# RefOsc10MHz_3V0.net
KiCad netlist of a schematic drawn in EAGLE
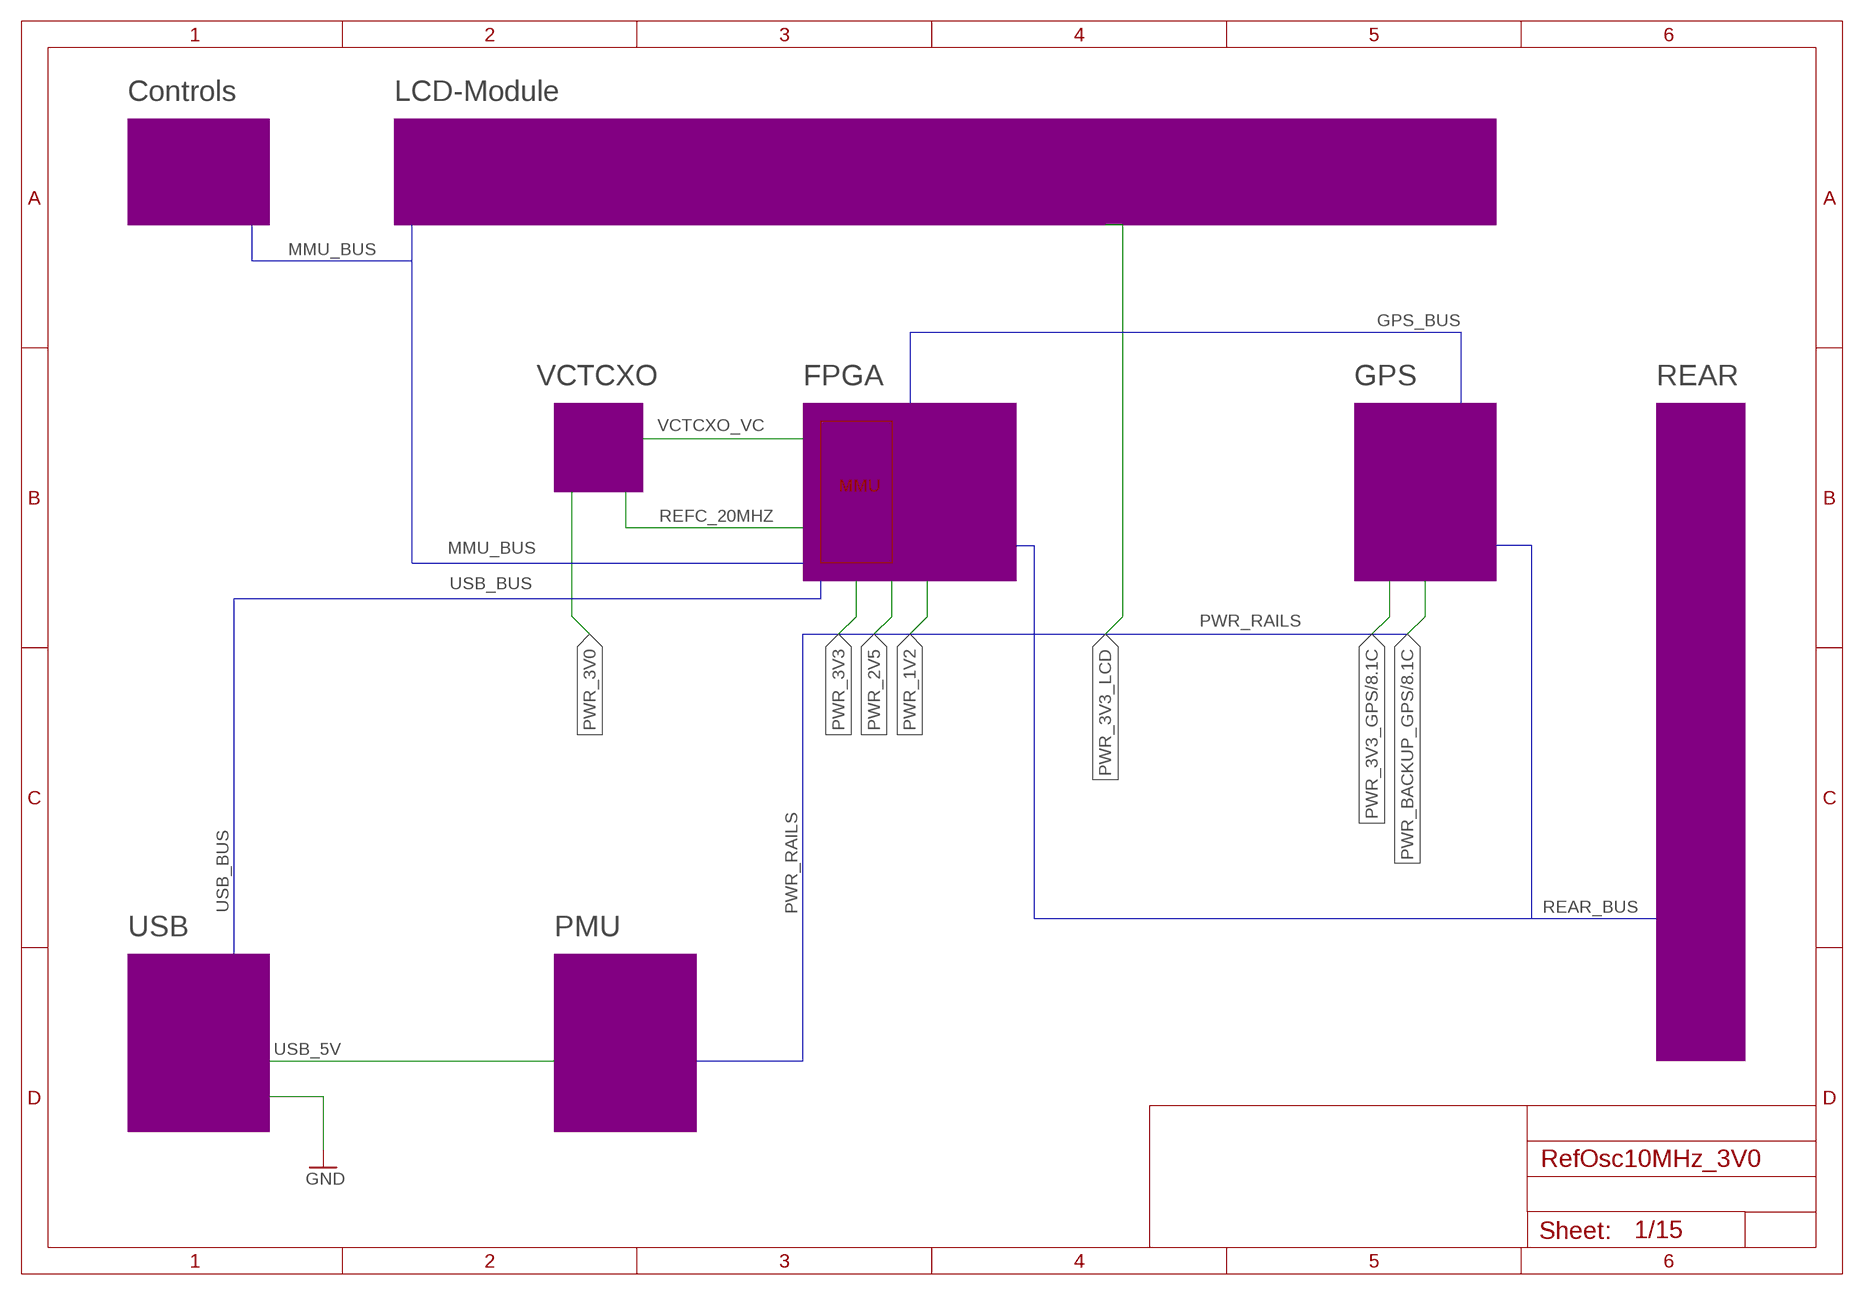
[diagram p0: schematic, sheet 1]
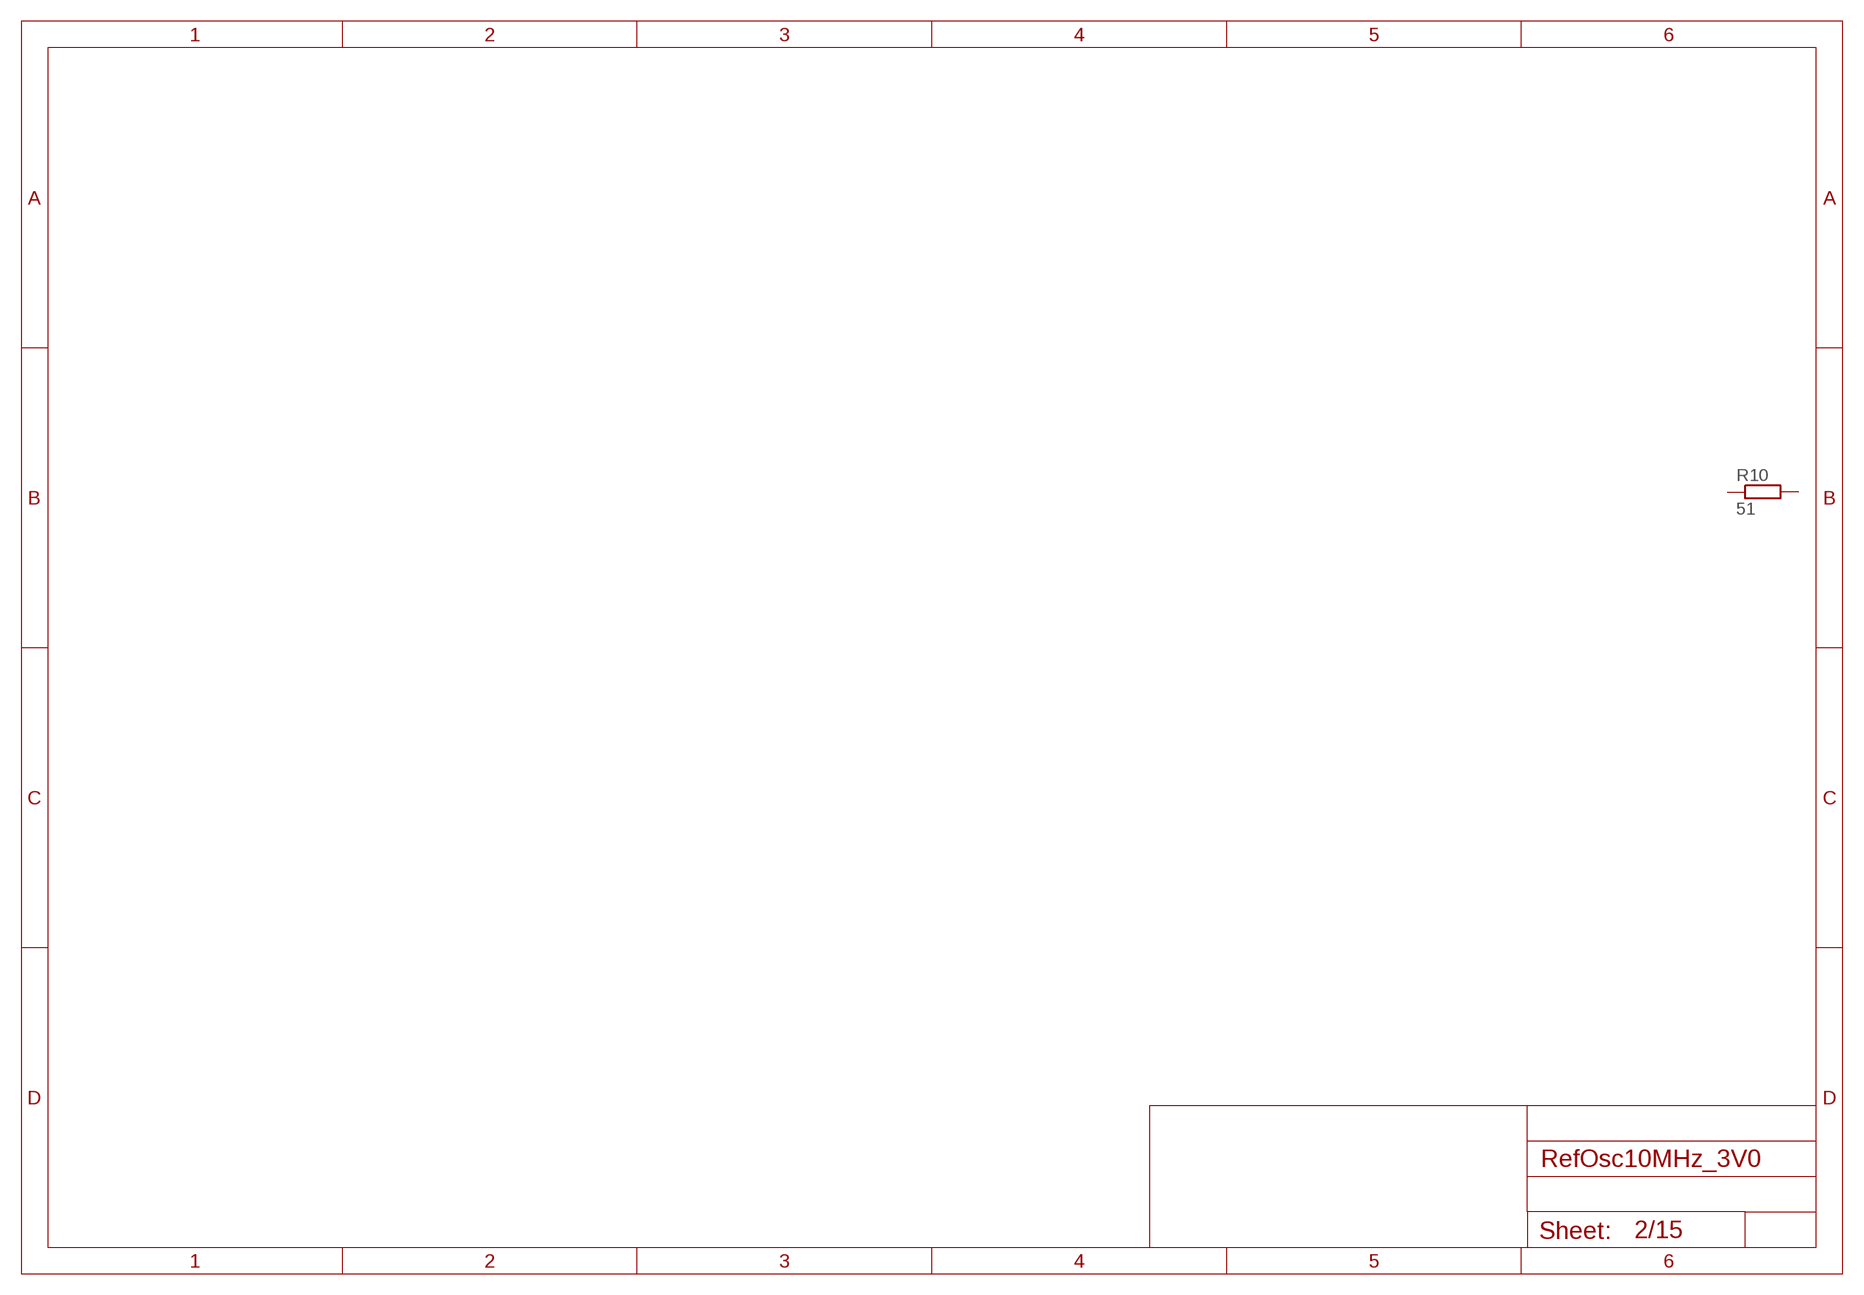
[diagram p1: schematic, sheet 2]
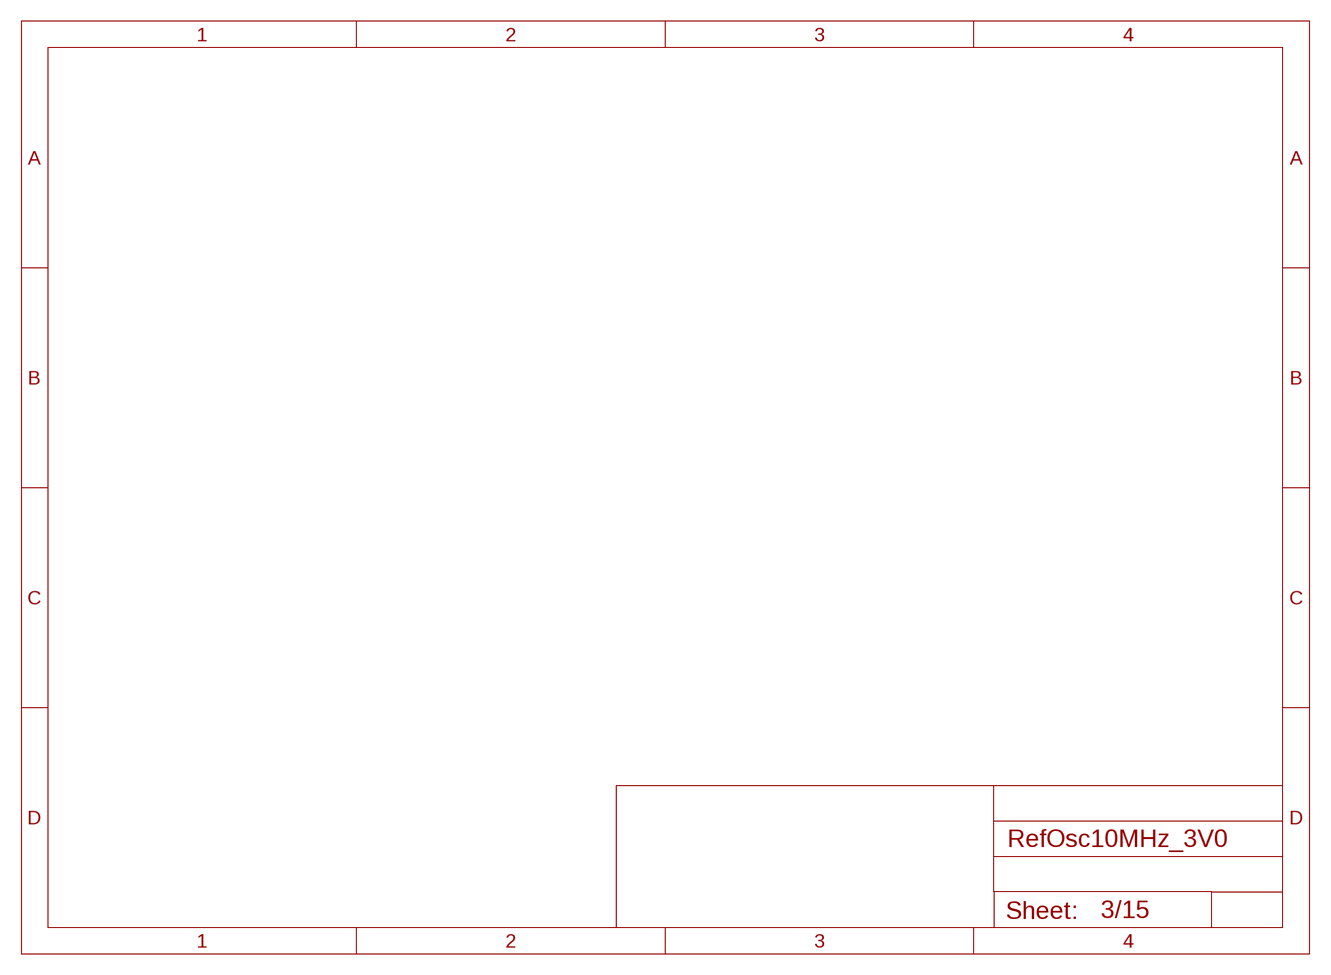
[diagram p2: schematic, sheet 3]
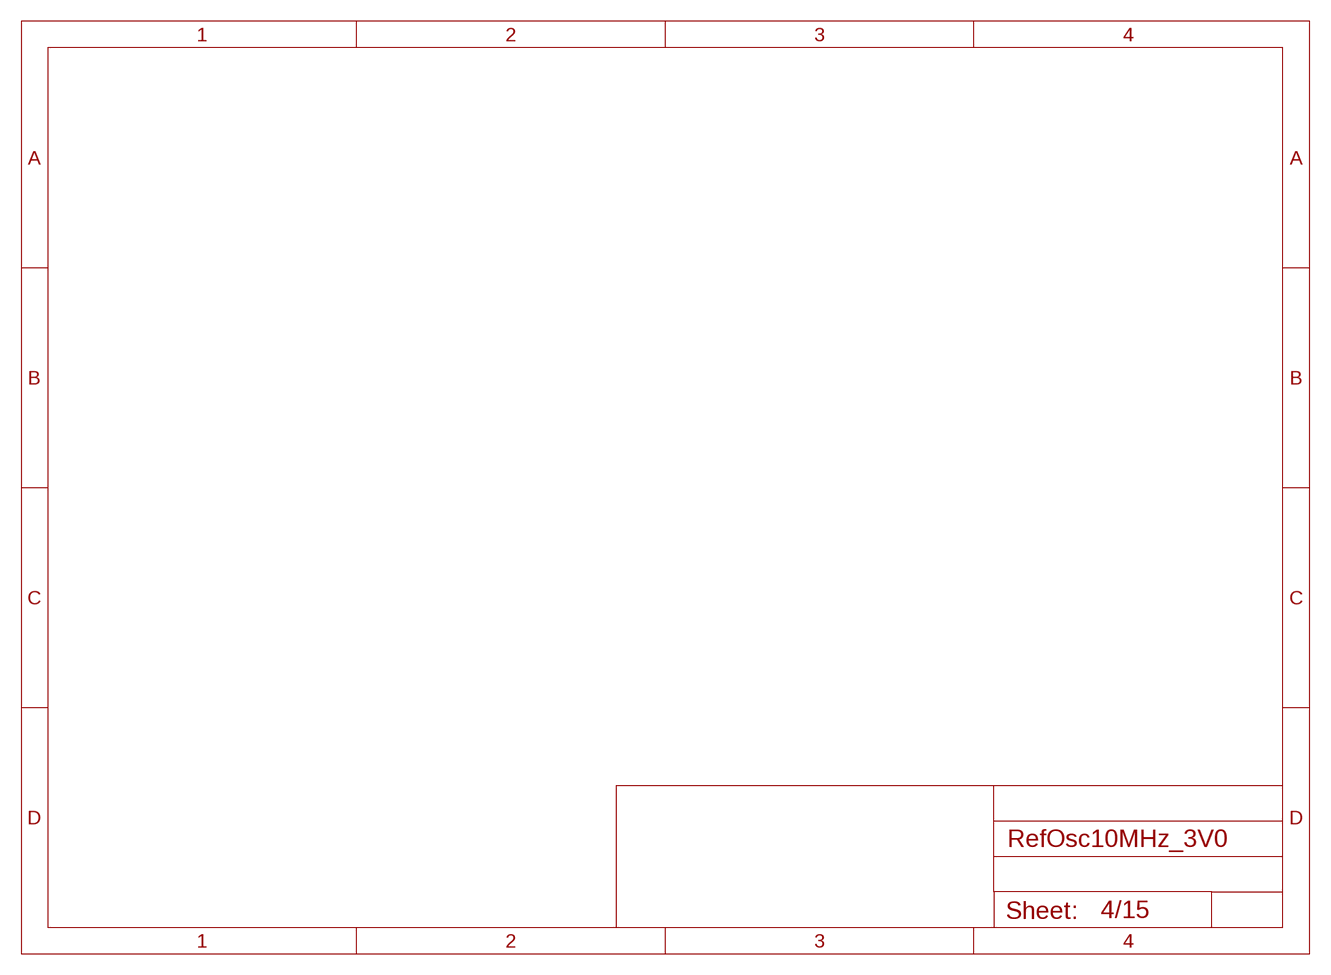
[diagram p3: schematic, sheet 4]
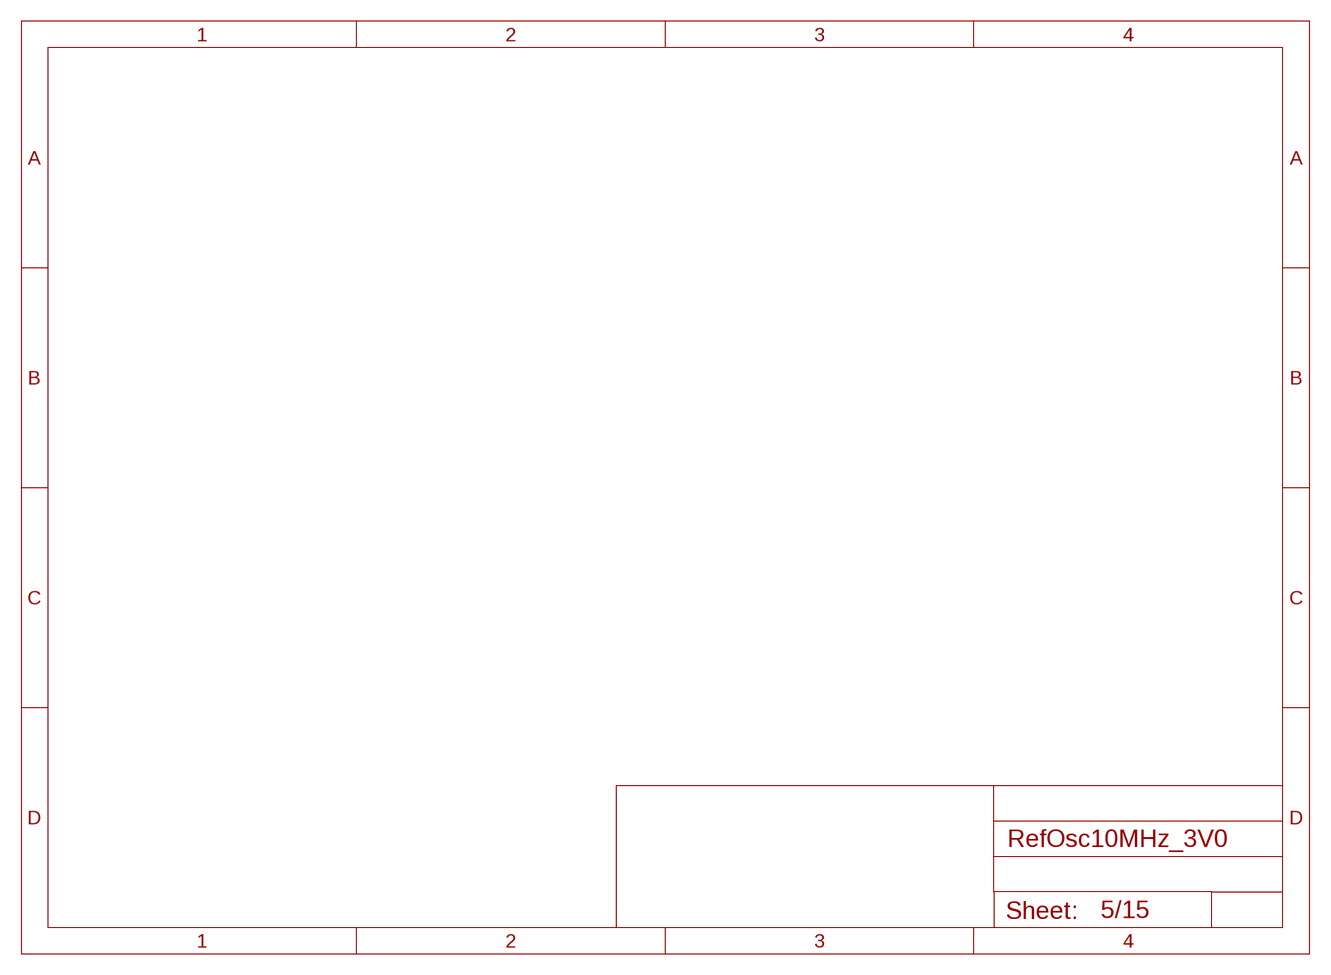
[diagram p4: schematic, sheet 5]
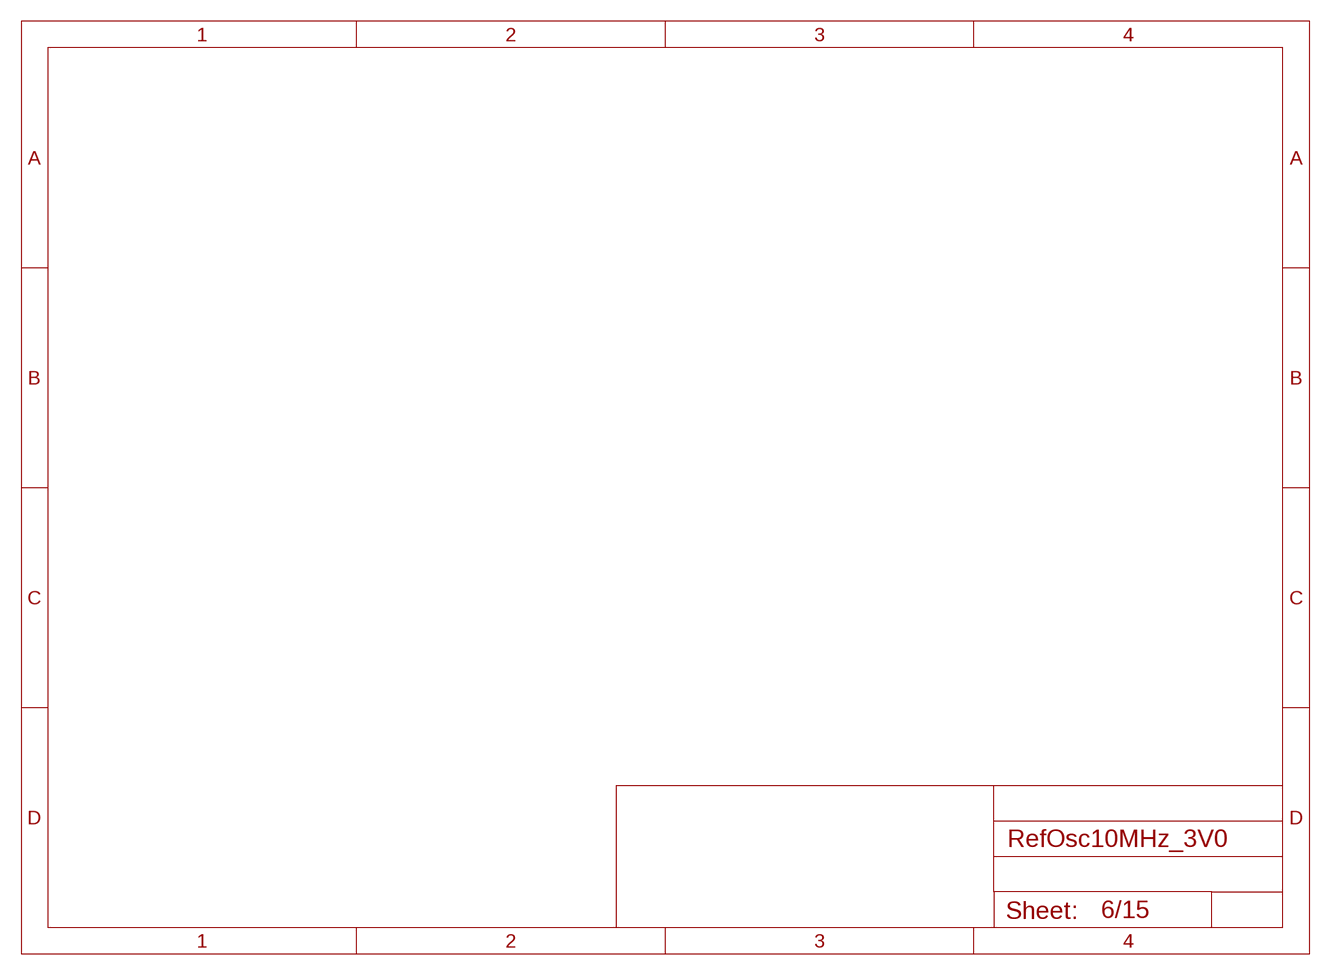
[diagram p5: schematic, sheet 6]
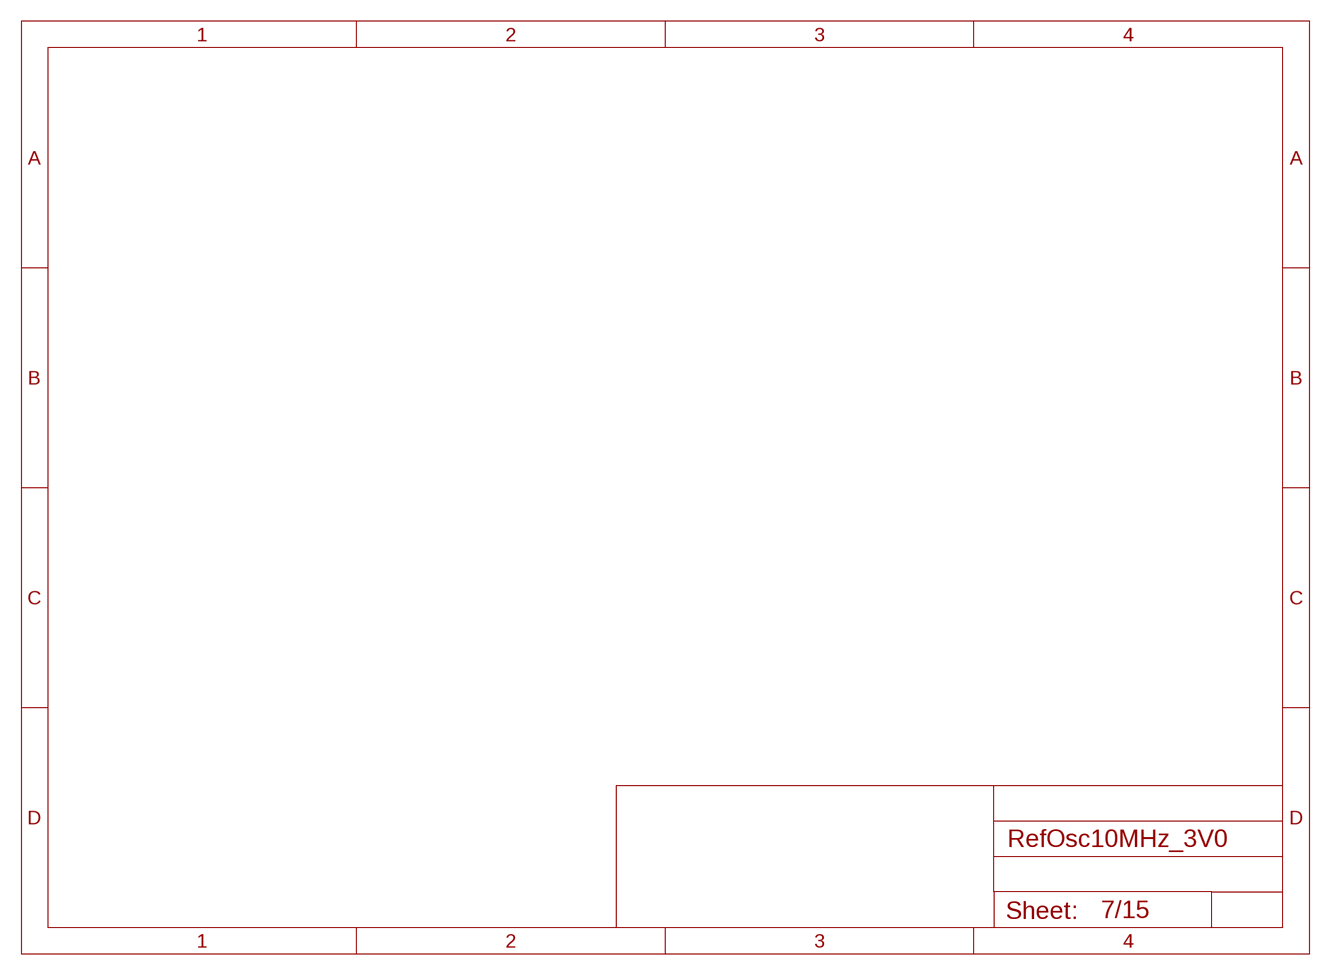
[diagram p6: schematic, sheet 7]
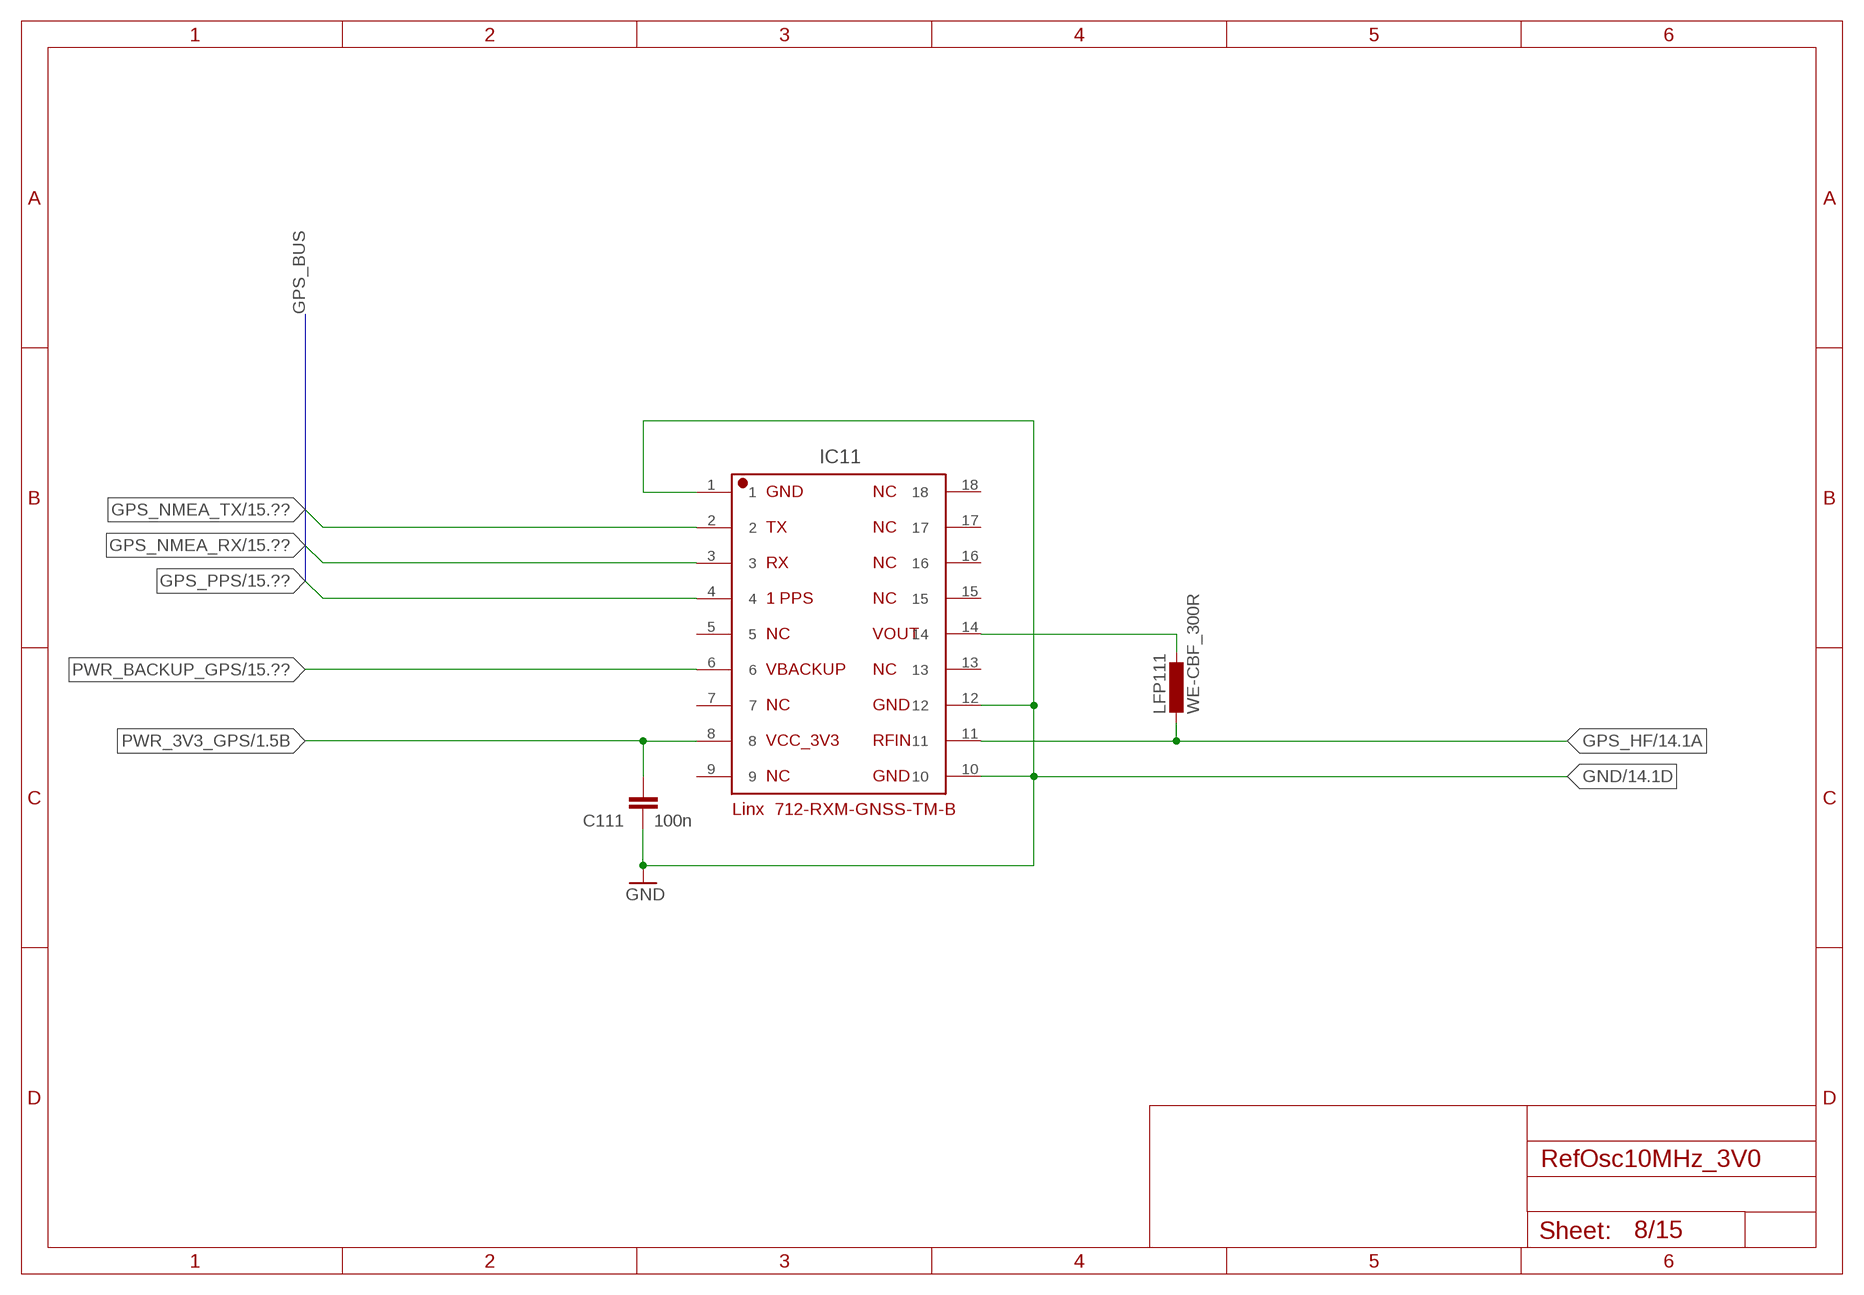
[diagram p7: schematic, sheet 8]
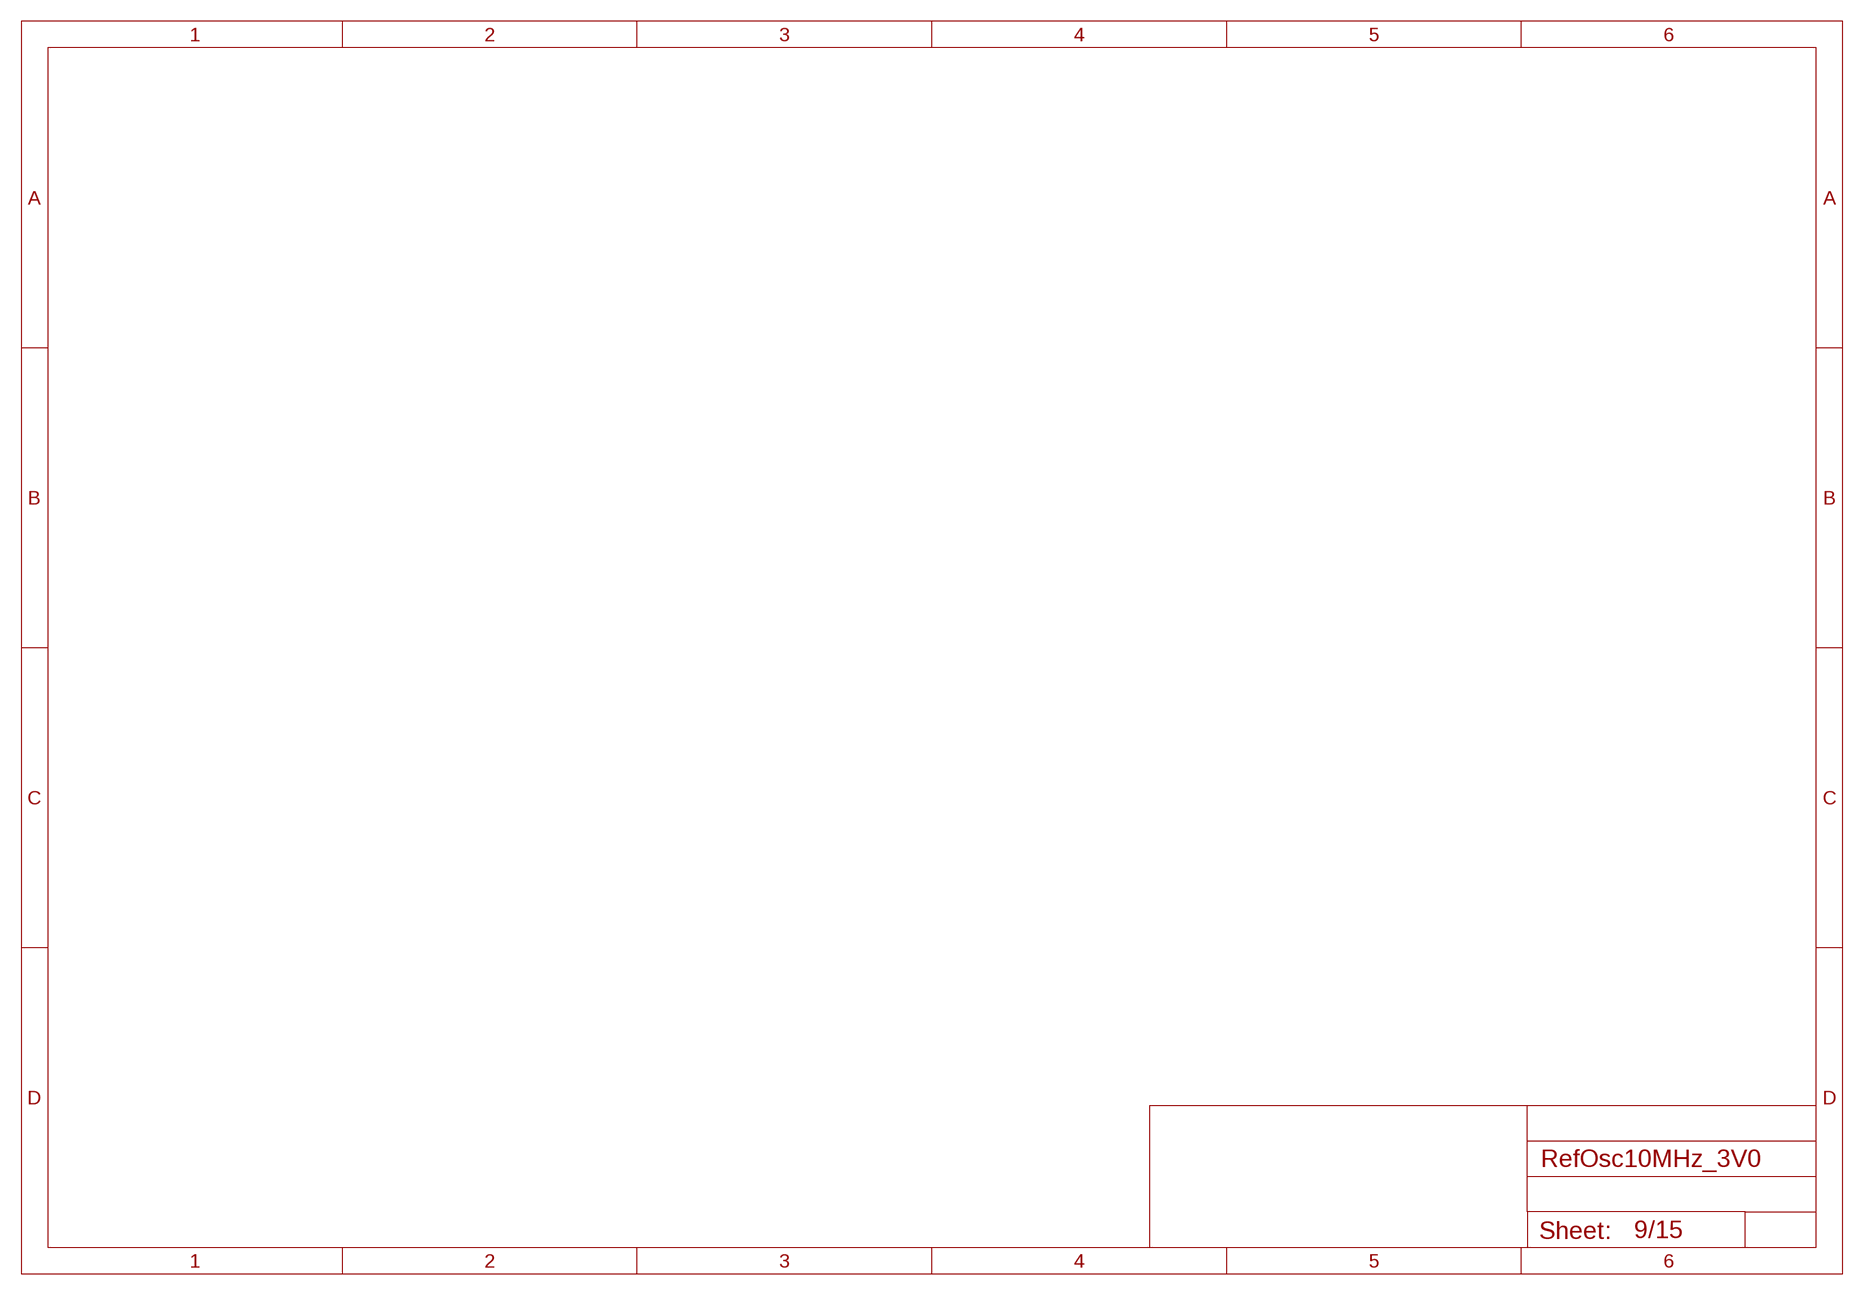
[diagram p8: schematic, sheet 9]
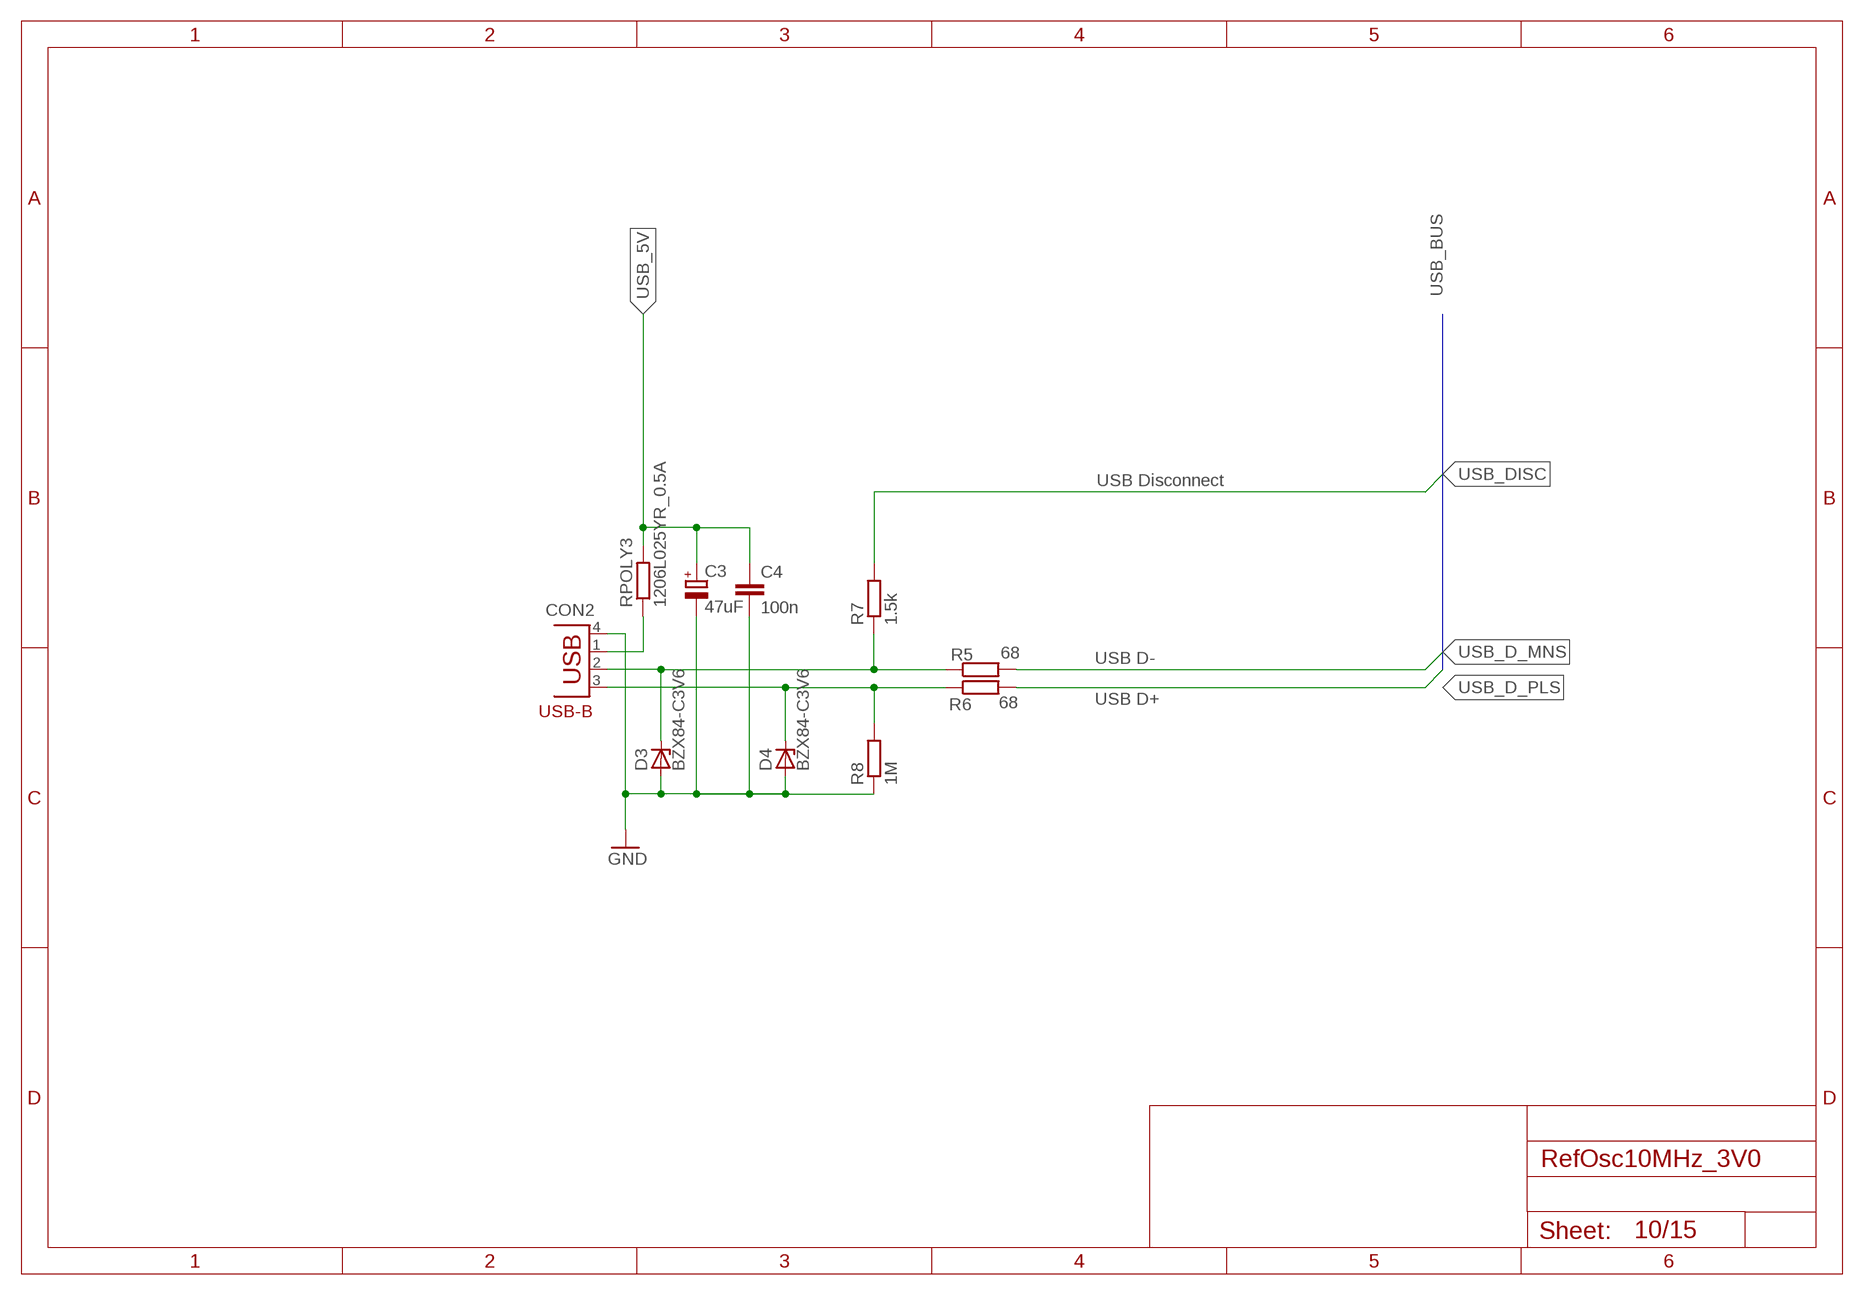
[diagram p9: schematic, sheet 10]
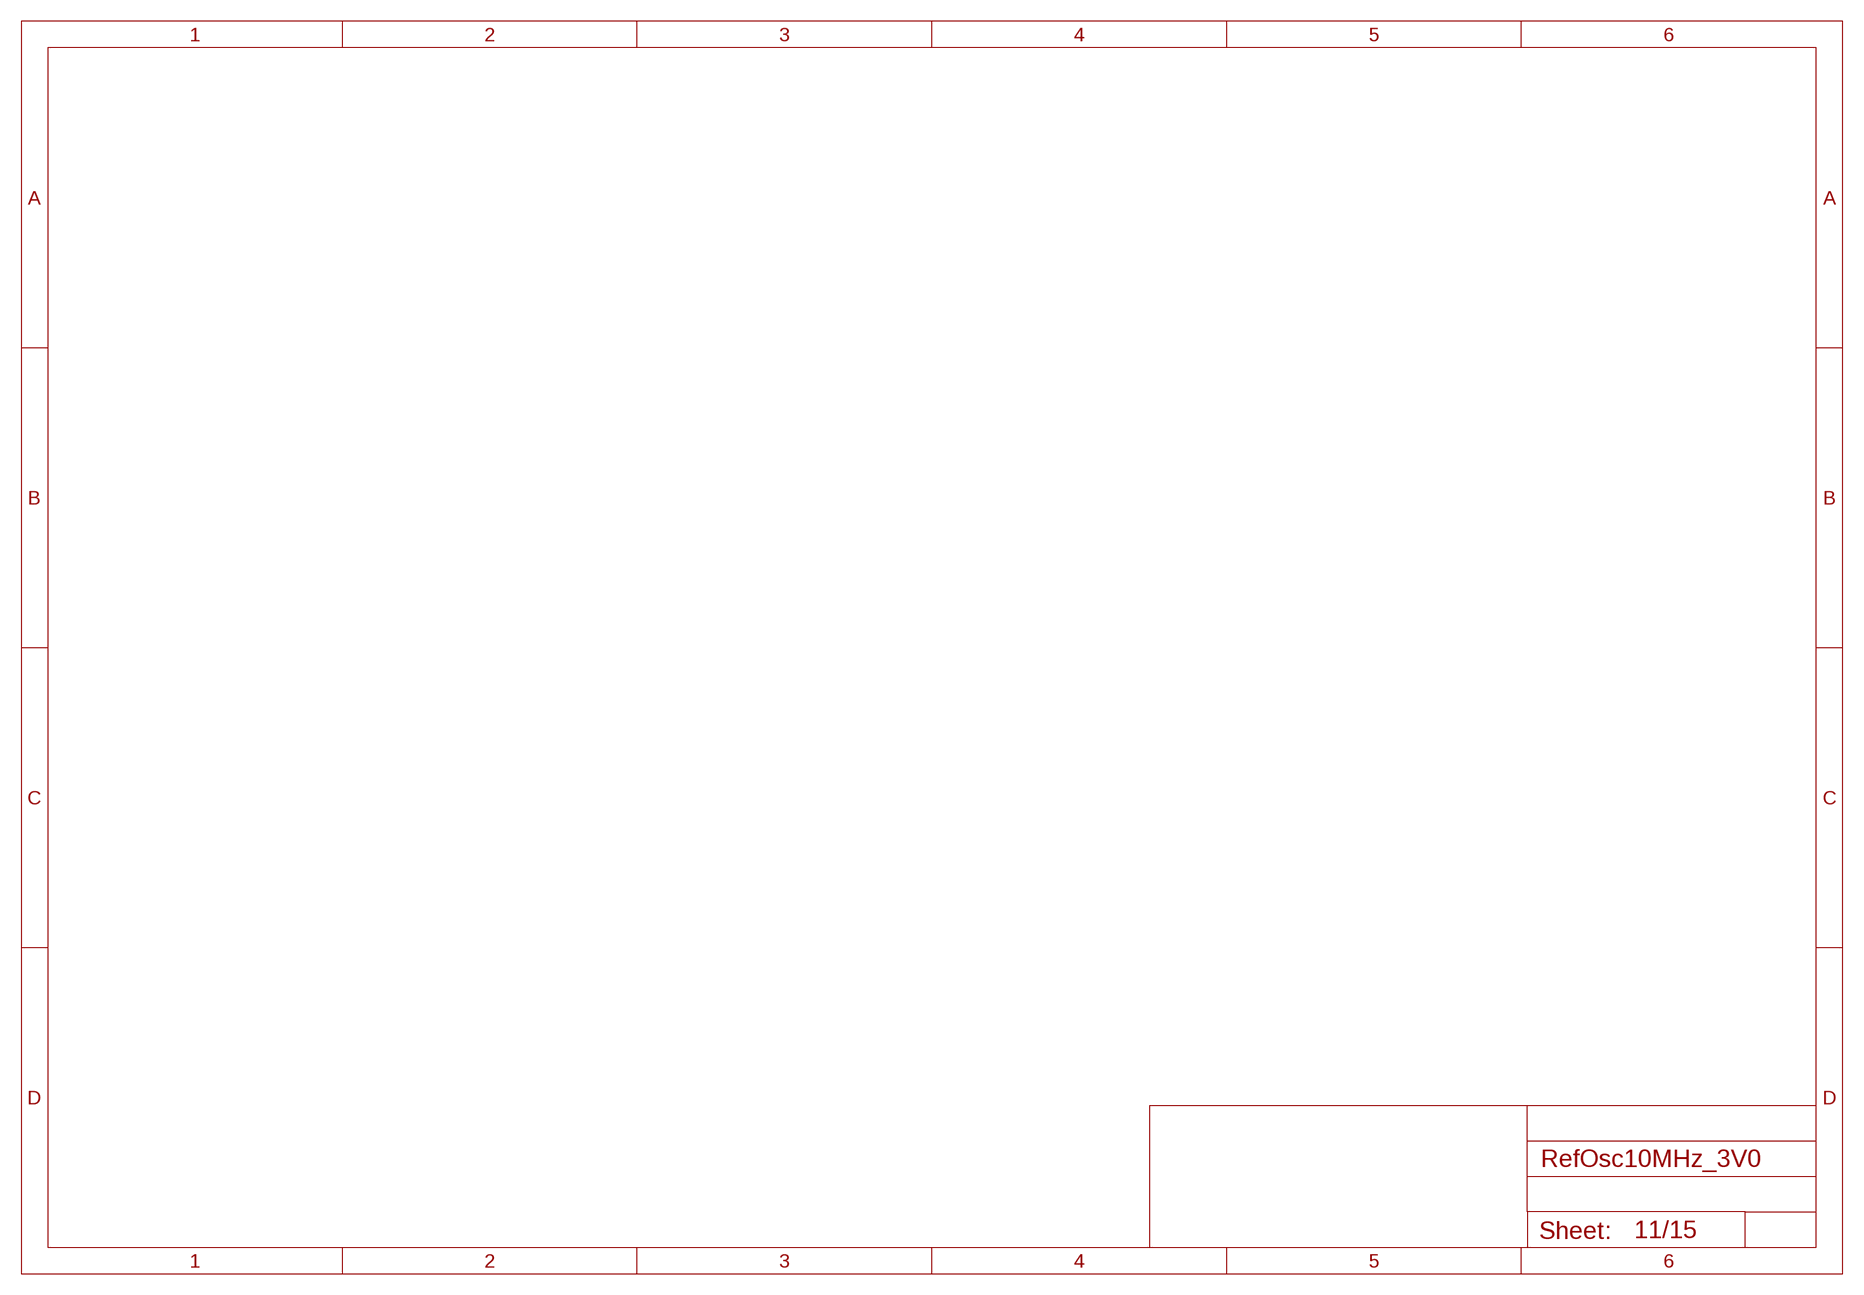
[diagram p10: schematic, sheet 11]
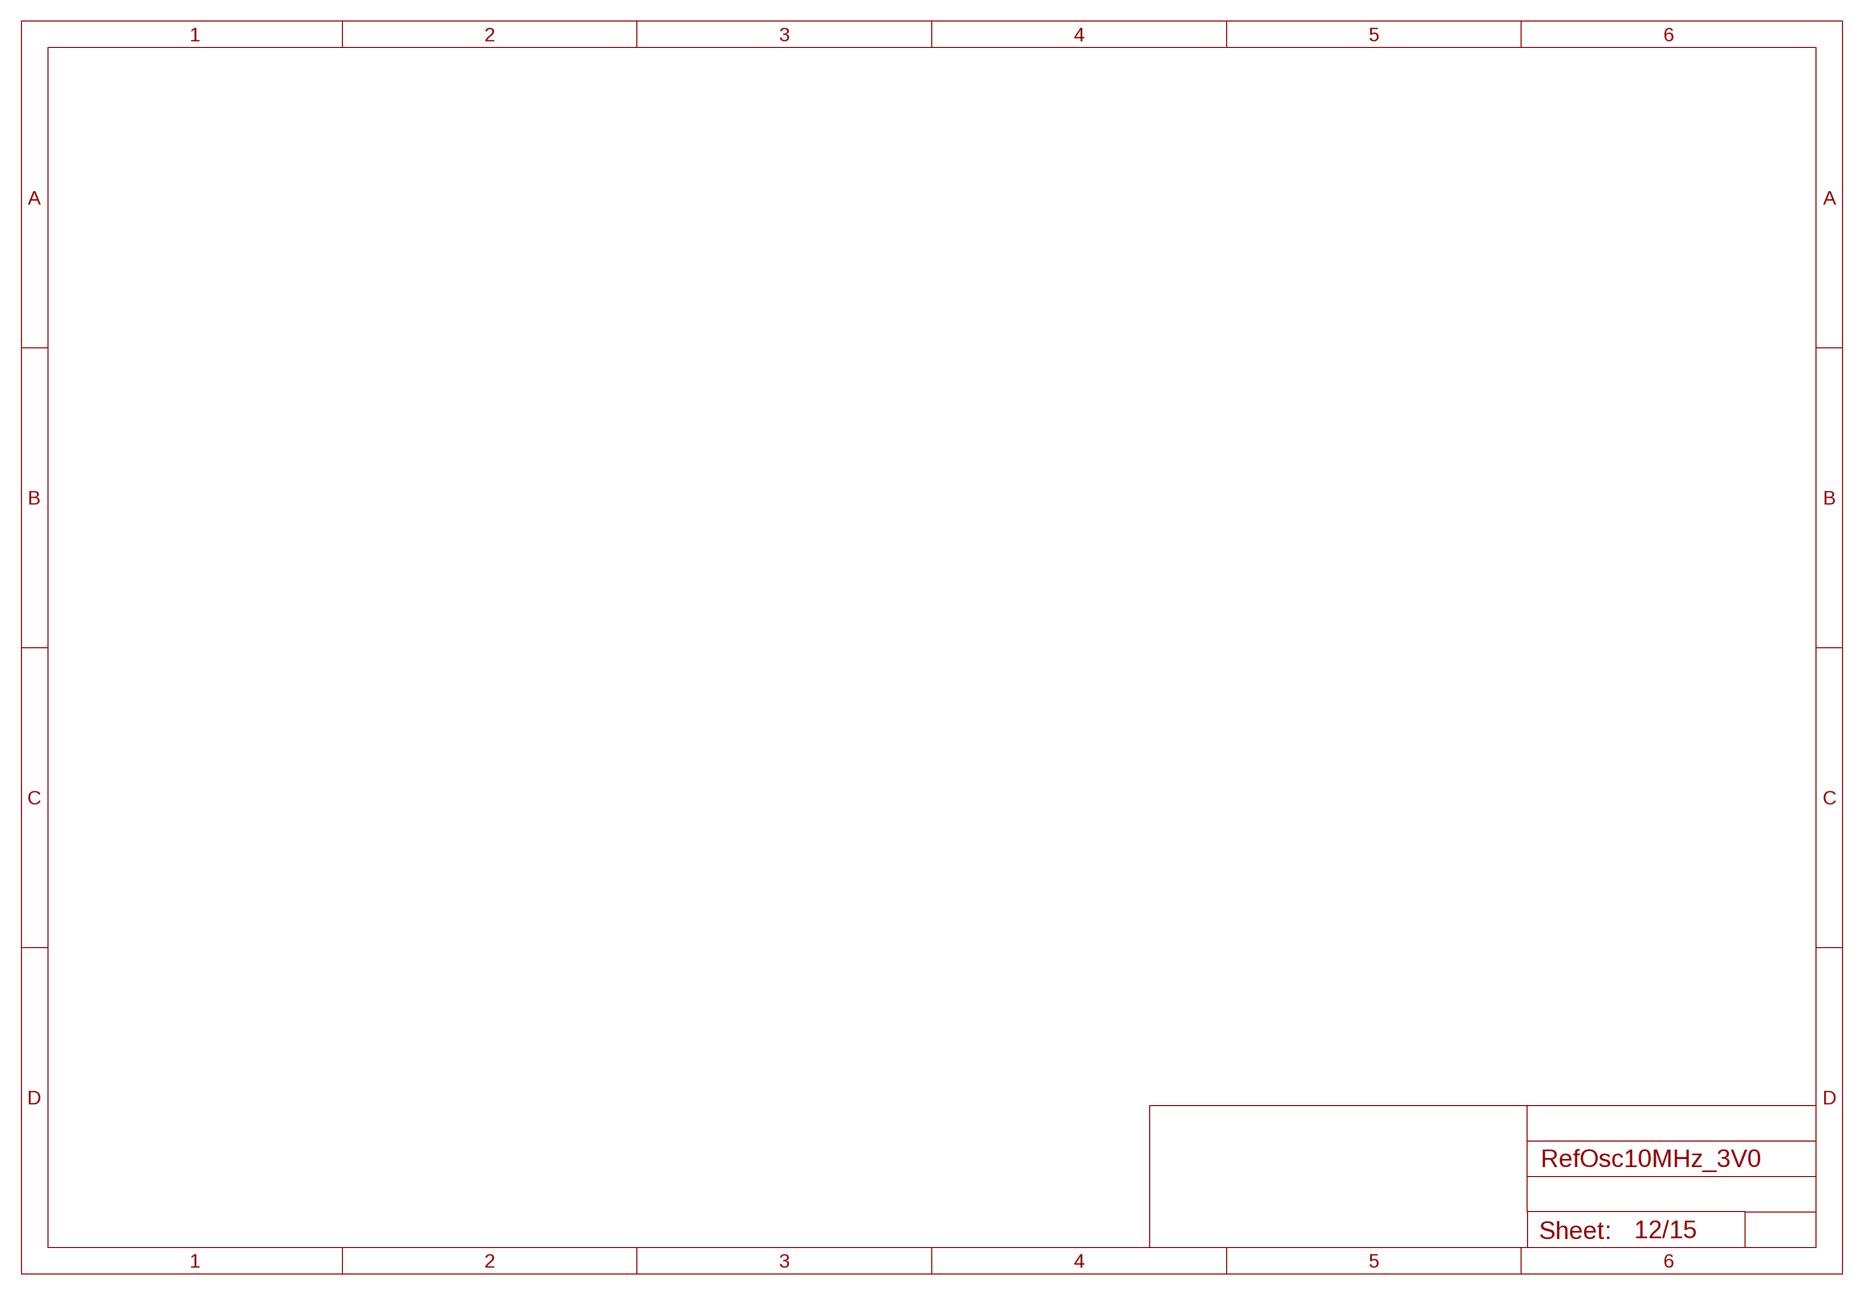
[diagram p11: schematic, sheet 12]
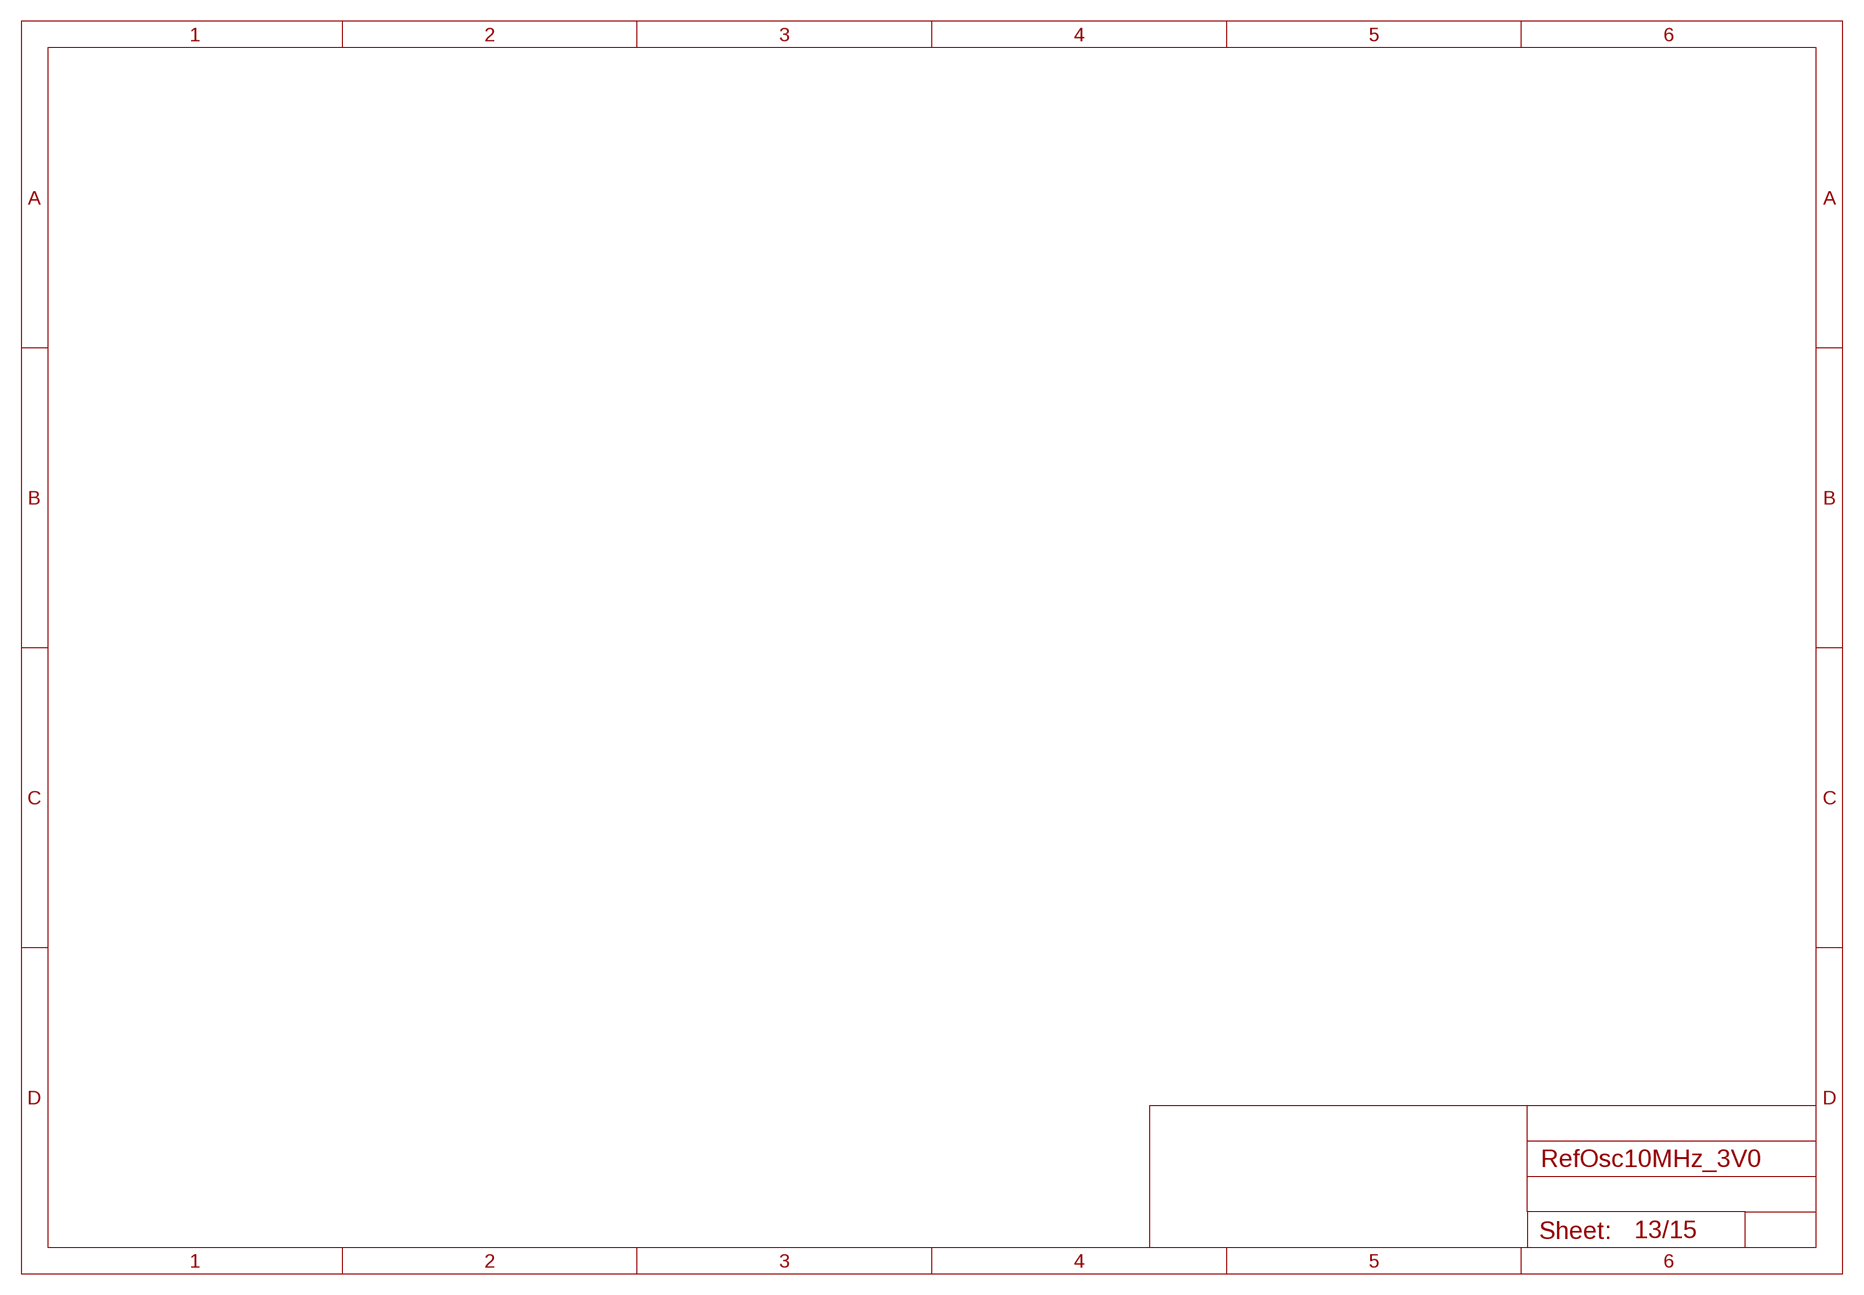
[diagram p12: schematic, sheet 13]
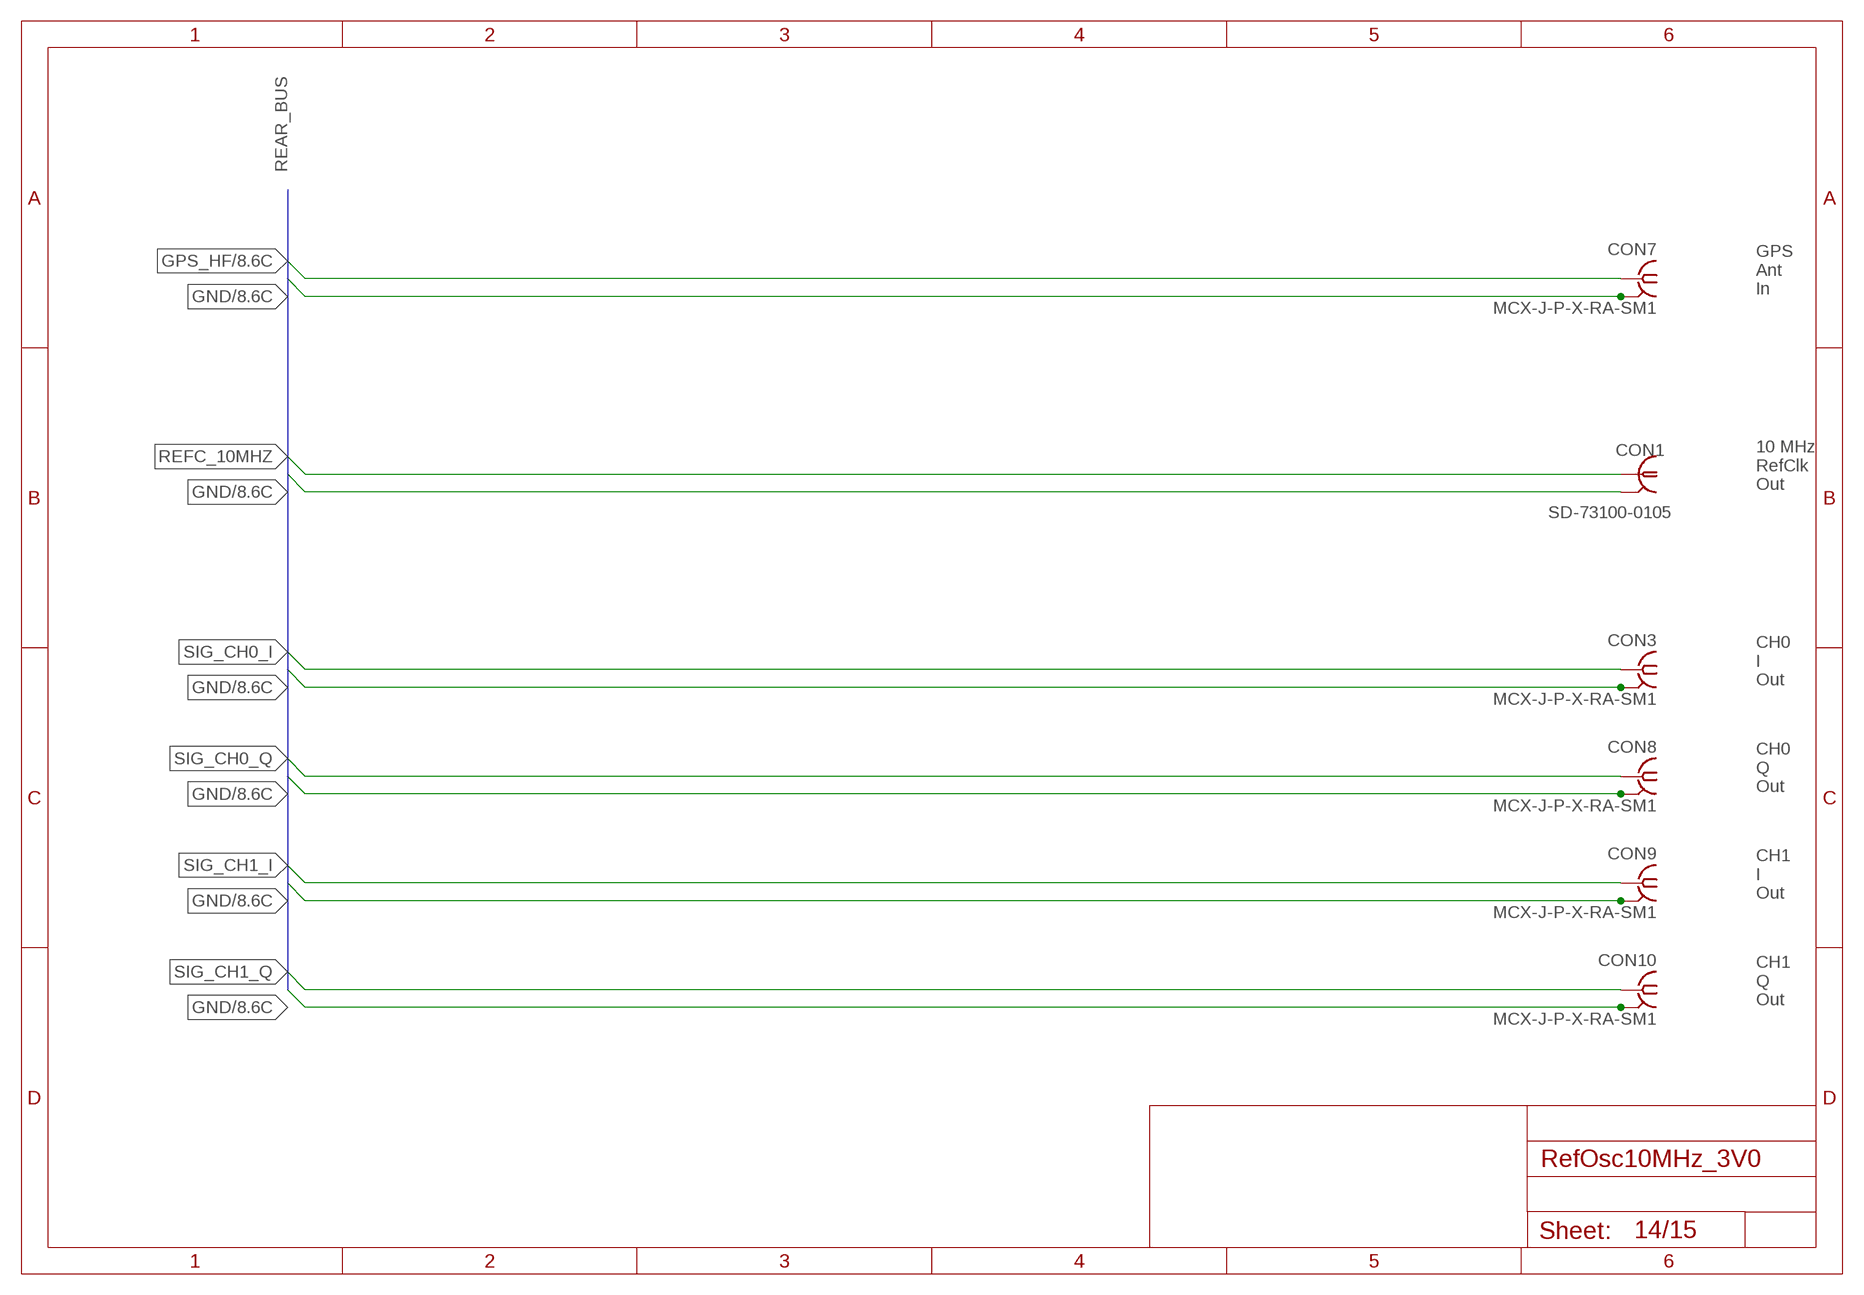
[diagram p13: schematic, sheet 14]
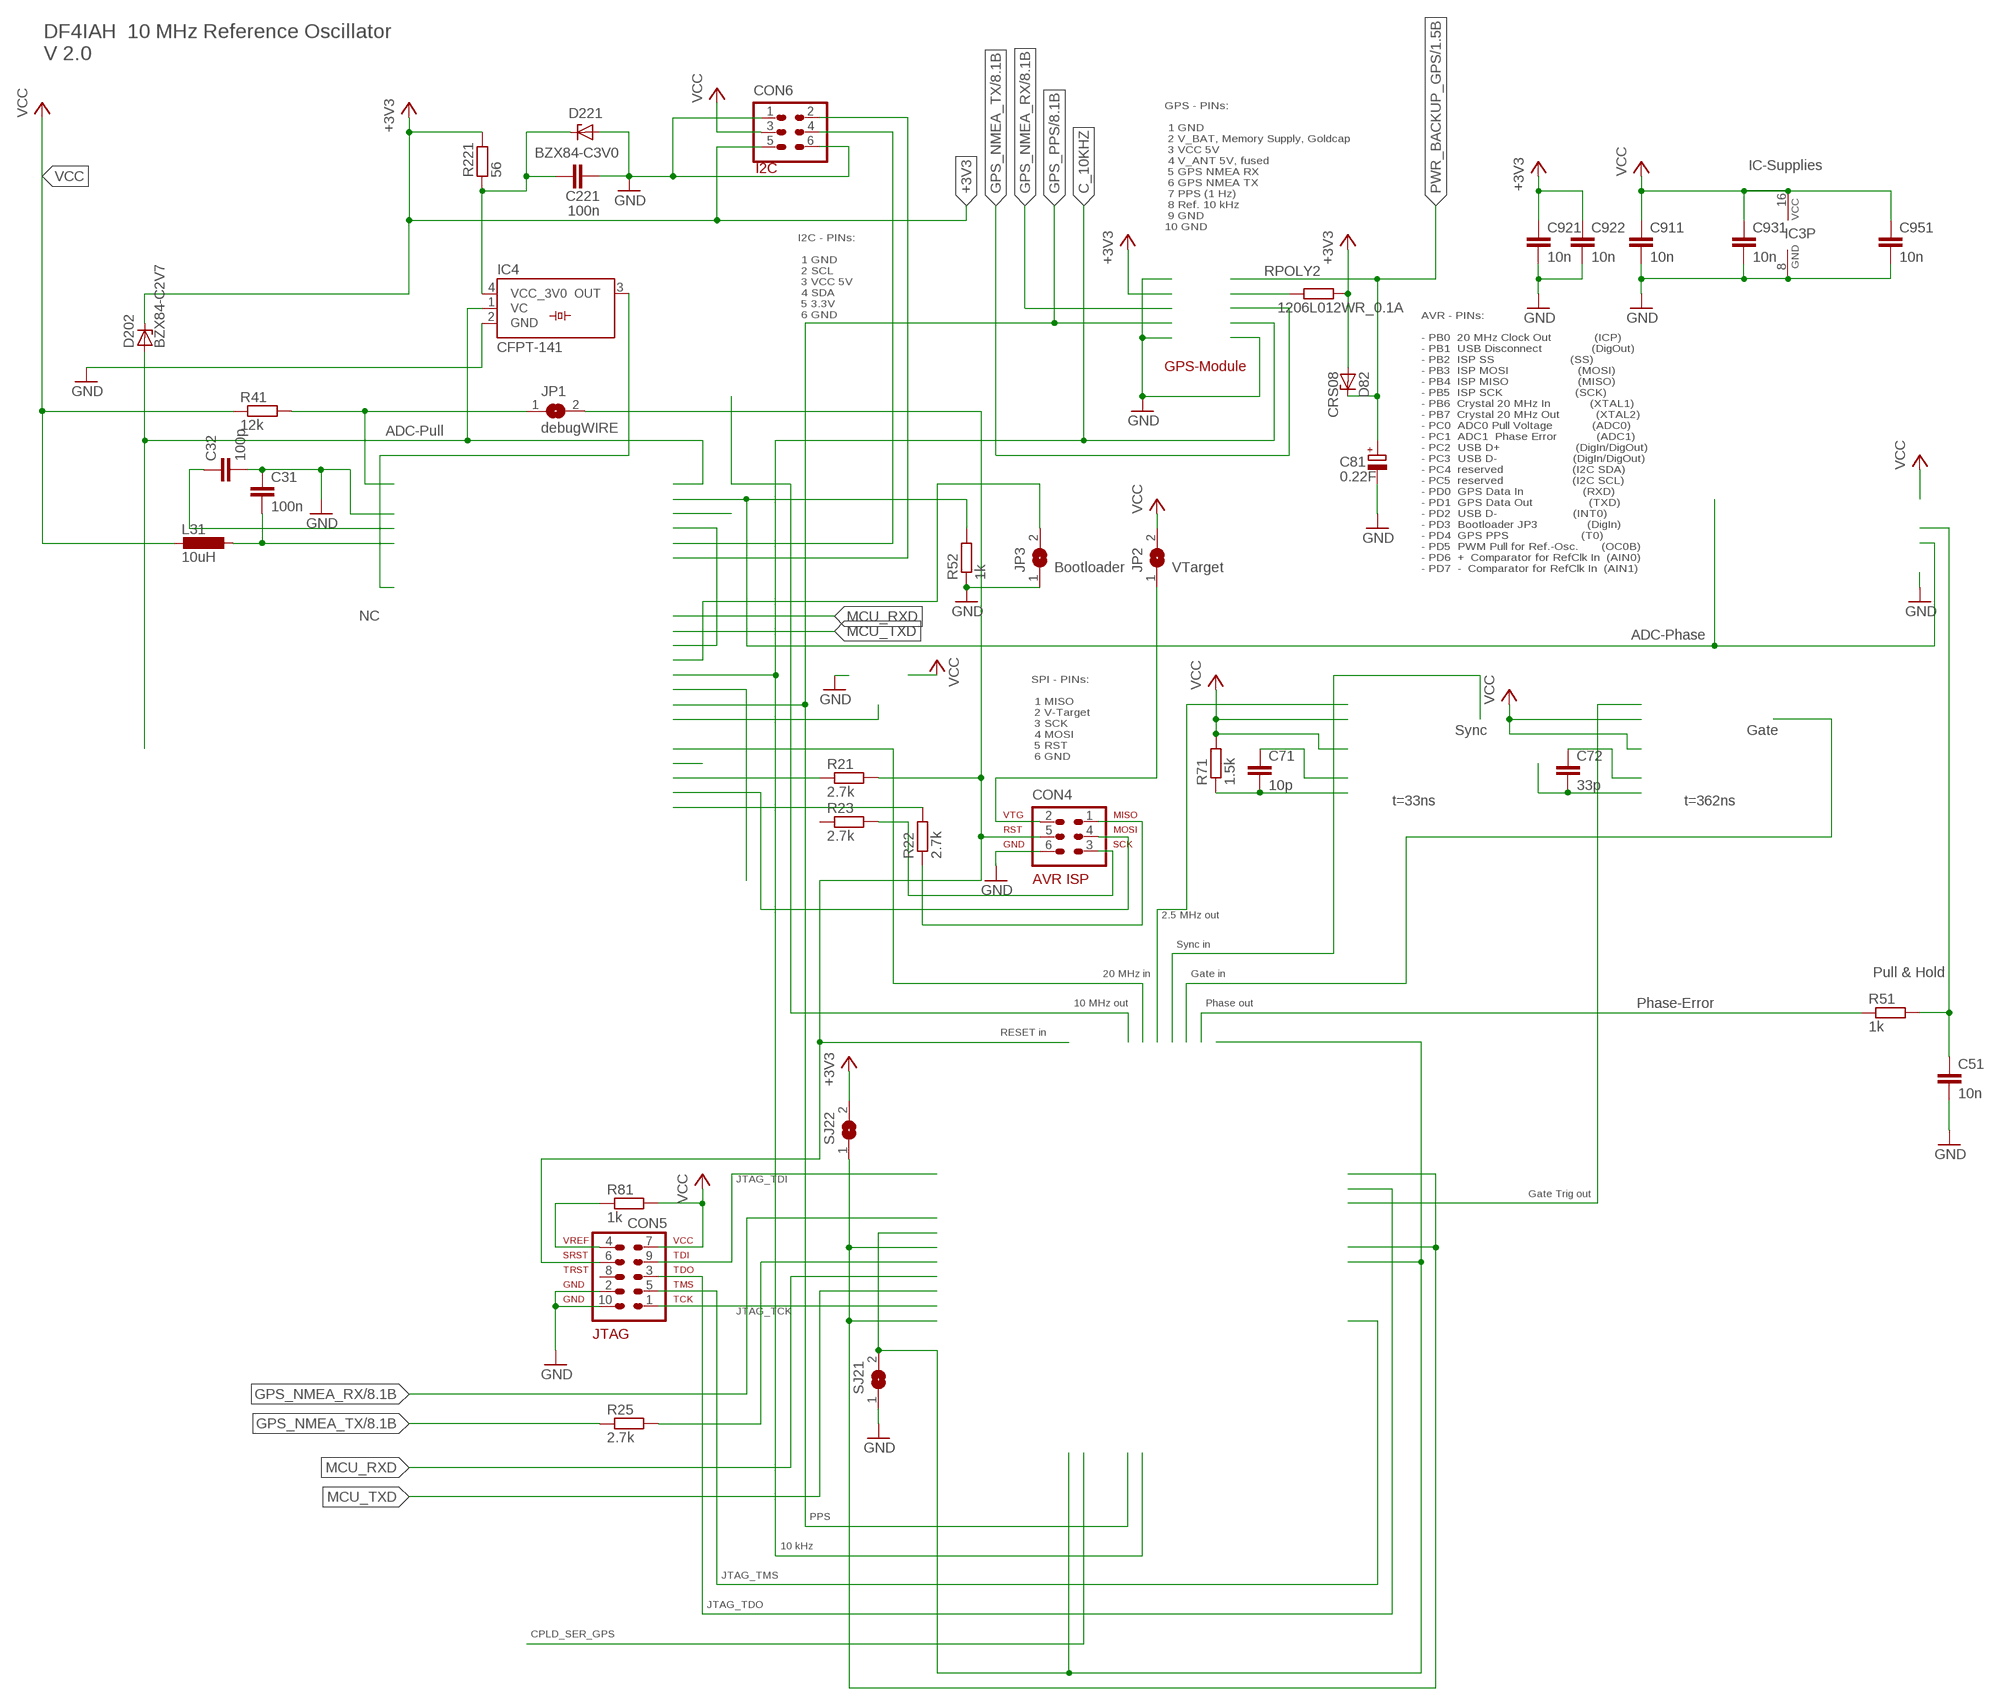
[diagram p14: schematic, sheet 15]

(export (version "E")
  (design (tool "Eeschema 10.0.6"))
  (components
    (comp (ref "CON1")
      (value "SD-73100-0105")
      (footprint "eagle-import:MOLEX_BNC-JACK-50R_SD-73100-0105")
      (fields (field (name "MF") "MOLEX"))
      (libsource (lib "eagle-import") (part "MOLEX_BNC-JACK-50R_SD-73100-0105"))
    )
    (comp (ref "CON3")
      (value "MCX-J-P-X-RA-SM1")
      (footprint "eagle-import:MCX-J-P-X-RA-SM1")
      (libsource (lib "eagle-import") (part "MCX-J-P-X-RA-SM1"))
    )
    (comp (ref "CON7")
      (value "MCX-J-P-X-RA-SM1")
      (footprint "eagle-import:MCX-J-P-X-RA-SM1")
      (libsource (lib "eagle-import") (part "MCX-J-P-X-RA-SM1"))
    )
    (comp (ref "CON8")
      (value "MCX-J-P-X-RA-SM1")
      (footprint "eagle-import:MCX-J-P-X-RA-SM1")
      (libsource (lib "eagle-import") (part "MCX-J-P-X-RA-SM1"))
    )
    (comp (ref "CON9")
      (value "MCX-J-P-X-RA-SM1")
      (footprint "eagle-import:MCX-J-P-X-RA-SM1")
      (libsource (lib "eagle-import") (part "MCX-J-P-X-RA-SM1"))
    )
    (comp (ref "CON10")
      (value "MCX-J-P-X-RA-SM1")
      (footprint "eagle-import:MCX-J-P-X-RA-SM1")
      (libsource (lib "eagle-import") (part "MCX-J-P-X-RA-SM1"))
    )
    (comp (ref "C31")
      (value "100n")
      (footprint "eagle-import:C0805")
      (libsource (lib "eagle-import") (part "rcl_C-EUC0805"))
    )
    (comp (ref "C32")
      (value "100p")
      (footprint "eagle-import:C0805")
      (libsource (lib "eagle-import") (part "rcl_C-EUC0805"))
    )
    (comp (ref "C51")
      (value "10n")
      (footprint "eagle-import:C0805")
      (libsource (lib "eagle-import") (part "rcl_C-EUC0805"))
    )
    (comp (ref "C71")
      (value "10p")
      (footprint "eagle-import:C0805")
      (libsource (lib "eagle-import") (part "rcl_C-EUC0805"))
    )
    (comp (ref "C72")
      (value "33p")
      (footprint "eagle-import:C0805")
      (libsource (lib "eagle-import") (part "rcl_C-EUC0805"))
    )
    (comp (ref "C81")
      (value "0.22F")
      (footprint "eagle-import:PANASONIC_C")
      (libsource (lib "eagle-import") (part "CPOL-EUC"))
    )
    (comp (ref "C221")
      (value "100n")
      (footprint "eagle-import:C0805")
      (libsource (lib "eagle-import") (part "rcl_C-EUC0805"))
    )
    (comp (ref "C911")
      (value "10n")
      (footprint "eagle-import:C0805")
      (libsource (lib "eagle-import") (part "rcl_C-EUC0805"))
    )
    (comp (ref "C921")
      (value "10n")
      (footprint "eagle-import:C0805")
      (libsource (lib "eagle-import") (part "rcl_C-EUC0805"))
    )
    (comp (ref "C922")
      (value "10n")
      (footprint "eagle-import:C0805")
      (libsource (lib "eagle-import") (part "rcl_C-EUC0805"))
    )
    (comp (ref "C931")
      (value "10n")
      (footprint "eagle-import:C0805")
      (libsource (lib "eagle-import") (part "rcl_C-EUC0805"))
    )
    (comp (ref "C951")
      (value "10n")
      (footprint "eagle-import:C0805")
      (libsource (lib "eagle-import") (part "rcl_C-EUC0805"))
    )
    (comp (ref "CON4")
      (value "AVR-ISP-6SMD")
      (footprint "eagle-import:2X3SMD")
      (libsource (lib "eagle-import") (part "AVR-ISP-6SMD"))
    )
    (comp (ref "CON5")
      (value "AVR-JTAG-10SMD")
      (footprint "eagle-import:2X5SMD")
      (libsource (lib "eagle-import") (part "AVR-JTAG-10SMD"))
    )
    (comp (ref "CON6")
      (value "HEADER-2X3SMD")
      (footprint "eagle-import:2X03SMD")
      (libsource (lib "eagle-import") (part "HEADER-2X3SMD"))
    )
    (comp (ref "D82")
      (value "CRS08")
      (footprint "eagle-import:SOT23")
      (libsource (lib "eagle-import") (part "ZENER-DIODESOT23"))
    )
    (comp (ref "D202")
      (value "BZX84-C2V7")
      (footprint "eagle-import:TO236")
      (libsource (lib "eagle-import") (part "BZX84CSMD"))
    )
    (comp (ref "D221")
      (value "BZX84-C3V0")
      (footprint "eagle-import:TO236")
      (libsource (lib "eagle-import") (part "BZX84CSMD"))
    )
    (comp (ref "IC3")
      (value "74HCT221D")
      (footprint "eagle-import:SO16")
      (libsource (lib "eagle-import") (part "74221DHCT"))
    )
    (comp (ref "IC4")
      (value "CFPT-141")
      (footprint "eagle-import:CFPT-141")
      (fields (field (name "MF") "IQD-FREQUENCY-PRODUCTS") (field (name "MPN") "LFTVXO022175"))
      (libsource (lib "eagle-import") (part "CFPT-141"))
    )
    (comp (ref "JP1")
      (value "SJW")
      (footprint "eagle-import:SJW")
      (libsource (lib "eagle-import") (part "SJW"))
    )
    (comp (ref "JP2")
      (value "SJW")
      (footprint "eagle-import:SJW")
      (libsource (lib "eagle-import") (part "SJW"))
    )
    (comp (ref "JP3")
      (value "SJW")
      (footprint "eagle-import:SJW")
      (libsource (lib "eagle-import") (part "SJW"))
    )
    (comp (ref "L31")
      (value "10uH")
      (footprint "eagle-import:L1812")
      (libsource (lib "eagle-import") (part "rcl_L-EUL1812"))
    )
    (comp (ref "R21")
      (value "2.7k")
      (footprint "eagle-import:R0805")
      (libsource (lib "eagle-import") (part "R-EU_R0805"))
    )
    (comp (ref "R22")
      (value "2.7k")
      (footprint "eagle-import:R0805")
      (libsource (lib "eagle-import") (part "R-EU_R0805"))
    )
    (comp (ref "R23")
      (value "2.7k")
      (footprint "eagle-import:R0805")
      (libsource (lib "eagle-import") (part "R-EU_R0805"))
    )
    (comp (ref "R25")
      (value "2.7k")
      (footprint "eagle-import:R0805")
      (libsource (lib "eagle-import") (part "R-EU_R0805"))
    )
    (comp (ref "R41")
      (value "12k")
      (footprint "eagle-import:R0805")
      (libsource (lib "eagle-import") (part "R-EU_R0805"))
    )
    (comp (ref "R51")
      (value "1k")
      (footprint "eagle-import:R0805")
      (libsource (lib "eagle-import") (part "R-EU_R0805"))
    )
    (comp (ref "R52")
      (value "1k")
      (footprint "eagle-import:R0805")
      (libsource (lib "eagle-import") (part "R-EU_R0805"))
    )
    (comp (ref "R71")
      (value "1.5k")
      (footprint "eagle-import:R0805")
      (libsource (lib "eagle-import") (part "R-EU_R0805"))
    )
    (comp (ref "R81")
      (value "1k")
      (footprint "eagle-import:R0805")
      (libsource (lib "eagle-import") (part "R-EU_R0805"))
    )
    (comp (ref "R221")
      (value "56")
      (footprint "eagle-import:R0805")
      (libsource (lib "eagle-import") (part "R-EU_R0805"))
    )
    (comp (ref "RPOLY2")
      (value "1206L012WR_0.1A")
      (footprint "eagle-import:M1206")
      (libsource (lib "eagle-import") (part "R-EU_M1206"))
    )
    (comp (ref "SJ21")
      (value "SJ")
      (footprint "eagle-import:SJ")
      (libsource (lib "eagle-import") (part "SJ"))
    )
    (comp (ref "SJ22")
      (value "SJ")
      (footprint "eagle-import:SJ")
      (libsource (lib "eagle-import") (part "SJ"))
    )
    (comp (ref "C111")
      (value "100n")
      (footprint "eagle-import:C0805")
      (libsource (lib "eagle-import") (part "C-EUC0805"))
    )
    (comp (ref "IC11")
      (value "712-RXM-GNSS-TM-B")
      (footprint "eagle-import:712-RXM-GNSS-TM-B")
      (libsource (lib "eagle-import") (part "712-RXM-GNSS-TM-B"))
    )
    (comp (ref "LFP111")
      (value "WE-CBF_300R")
      (footprint "eagle-import:L3216C")
      (libsource (lib "eagle-import") (part "L-EUL3216C"))
    )
    (comp (ref "R10")
      (value "51")
      (footprint "eagle-import:R0805")
      (libsource (lib "eagle-import") (part "R-EU_R0805"))
    )
    (comp (ref "C3")
      (value "47uF")
      (footprint "eagle-import:PANASONIC_C")
      (libsource (lib "eagle-import") (part "CPOL-EUC"))
    )
    (comp (ref "C4")
      (value "100n")
      (footprint "eagle-import:C0805")
      (libsource (lib "eagle-import") (part "rcl_C-EUC0805"))
    )
    (comp (ref "CON2")
      (value "TYCO-AMP_USBUSB-B_SMT")
      (footprint "eagle-import:TYCO-AMP_USB-B_SMT")
      (fields (field (name "MF") "TYCO-AMP") (field (name "MPN") "1734346"))
      (libsource (lib "eagle-import") (part "TYCO-AMP_USBUSB-B_SMT"))
    )
    (comp (ref "D3")
      (value "BZX84-C3V6")
      (footprint "eagle-import:TO236")
      (libsource (lib "eagle-import") (part "BZX84CSMD"))
    )
    (comp (ref "D4")
      (value "BZX84-C3V6")
      (footprint "eagle-import:TO236")
      (libsource (lib "eagle-import") (part "BZX84CSMD"))
    )
    (comp (ref "R5")
      (value "68")
      (footprint "eagle-import:R0805")
      (libsource (lib "eagle-import") (part "R-EU_R0805"))
    )
    (comp (ref "R6")
      (value "68")
      (footprint "eagle-import:R0805")
      (libsource (lib "eagle-import") (part "R-EU_R0805"))
    )
    (comp (ref "R7")
      (value "1.5k")
      (footprint "eagle-import:R0805")
      (libsource (lib "eagle-import") (part "R-EU_R0805"))
    )
    (comp (ref "R8")
      (value "1M")
      (footprint "eagle-import:R0805")
      (libsource (lib "eagle-import") (part "R-EU_R0805"))
    )
    (comp (ref "RPOLY3")
      (value "1206L025YR_0.5A")
      (footprint "eagle-import:M1206")
      (libsource (lib "eagle-import") (part "R-EU_M1206"))
    )
  )
  (nets
    (net (code "9") (name "+3V3") (class "Default")
      (node (ref "C921") (pin "1") (pinfunction "1_1") (pintype "passive"))
      (node (ref "C922") (pin "1") (pinfunction "1_1") (pintype "passive"))
      (node (ref "CON6") (pin "5") (pinfunction "5_5") (pintype "passive"))
      (node (ref "D202") (pin "C") (pinfunction "C_C") (pintype "passive"))
      (node (ref "D82") (pin "1") (pinfunction "A_1") (pintype "passive"))
      (node (ref "R221") (pin "1") (pinfunction "1_1") (pintype "passive"))
      (node (ref "RPOLY2") (pin "2") (pinfunction "2_2") (pintype "passive"))
      (node (ref "SJ22") (pin "2") (pinfunction "2_2") (pintype "passive"))
    )
    (net (code "19") (name "GND") (class "Default")
      (node (ref "C111") (pin "2") (pinfunction "2_2") (pintype "passive"))
      (node (ref "C221") (pin "2") (pinfunction "2_2") (pintype "passive"))
      (node (ref "C3") (pin "-") (pinfunction "-_-") (pintype "passive"))
      (node (ref "C31") (pin "1") (pinfunction "1_1") (pintype "passive"))
      (node (ref "C32") (pin "2") (pinfunction "2_2") (pintype "passive"))
      (node (ref "C4") (pin "2") (pinfunction "2_2") (pintype "passive"))
      (node (ref "C51") (pin "2") (pinfunction "2_2") (pintype "passive"))
      (node (ref "C81") (pin "-") (pinfunction "-_-") (pintype "passive"))
      (node (ref "C911") (pin "2") (pinfunction "2_2") (pintype "passive"))
      (node (ref "C921") (pin "2") (pinfunction "2_2") (pintype "passive"))
      (node (ref "C922") (pin "2") (pinfunction "2_2") (pintype "passive"))
      (node (ref "C931") (pin "2") (pinfunction "2_2") (pintype "passive"))
      (node (ref "C951") (pin "2") (pinfunction "2_2") (pintype "passive"))
      (node (ref "CON1") (pin "2") (pinfunction "2_2") (pintype "passive"))
      (node (ref "CON1") (pin "3") (pinfunction "3_3") (pintype "passive"))
      (node (ref "CON10") (pin "2") (pinfunction "2_2") (pintype "passive"))
      (node (ref "CON10") (pin "3") (pinfunction "3_3") (pintype "passive"))
      (node (ref "CON10") (pin "4") (pinfunction "4_4") (pintype "passive"))
      (node (ref "CON10") (pin "5") (pinfunction "5_5") (pintype "passive"))
      (node (ref "CON2") (pin "4") (pinfunction "GND_4") (pintype "bidirectional"))
      (node (ref "CON3") (pin "2") (pinfunction "2_2") (pintype "passive"))
      (node (ref "CON3") (pin "3") (pinfunction "3_3") (pintype "passive"))
      (node (ref "CON3") (pin "4") (pinfunction "4_4") (pintype "passive"))
      (node (ref "CON3") (pin "5") (pinfunction "5_5") (pintype "passive"))
      (node (ref "CON4") (pin "6") (pinfunction "6_6") (pintype "passive"))
      (node (ref "CON5") (pin "10") (pinfunction "10_10") (pintype "passive"))
      (node (ref "CON5") (pin "2") (pinfunction "2_2") (pintype "passive"))
      (node (ref "CON6") (pin "1") (pinfunction "1_1") (pintype "passive"))
      (node (ref "CON6") (pin "6") (pinfunction "6_6") (pintype "passive"))
      (node (ref "CON7") (pin "2") (pinfunction "2_2") (pintype "passive"))
      (node (ref "CON7") (pin "3") (pinfunction "3_3") (pintype "passive"))
      (node (ref "CON7") (pin "4") (pinfunction "4_4") (pintype "passive"))
      (node (ref "CON7") (pin "5") (pinfunction "5_5") (pintype "passive"))
      (node (ref "CON8") (pin "2") (pinfunction "2_2") (pintype "passive"))
      (node (ref "CON8") (pin "3") (pinfunction "3_3") (pintype "passive"))
      (node (ref "CON8") (pin "4") (pinfunction "4_4") (pintype "passive"))
      (node (ref "CON8") (pin "5") (pinfunction "5_5") (pintype "passive"))
      (node (ref "CON9") (pin "2") (pinfunction "2_2") (pintype "passive"))
      (node (ref "CON9") (pin "3") (pinfunction "3_3") (pintype "passive"))
      (node (ref "CON9") (pin "4") (pinfunction "4_4") (pintype "passive"))
      (node (ref "CON9") (pin "5") (pinfunction "5_5") (pintype "passive"))
      (node (ref "D221") (pin "A") (pinfunction "A_A") (pintype "passive"))
      (node (ref "D3") (pin "A") (pinfunction "A_A") (pintype "passive"))
      (node (ref "D4") (pin "A") (pinfunction "A_A") (pintype "passive"))
      (node (ref "IC11") (pin "1") (pinfunction "1_1") (pintype "power_in"))
      (node (ref "IC11") (pin "10") (pinfunction "10_10") (pintype "power_in"))
      (node (ref "IC11") (pin "12") (pinfunction "12_12") (pintype "power_in"))
      (node (ref "IC3") (pin "8") (pinfunction "GND_8") (pintype "power_in"))
      (node (ref "IC4") (pin "2") (pinfunction "GND_2") (pintype "power_in"))
      (node (ref "JP3") (pin "1") (pinfunction "1_1") (pintype "passive"))
      (node (ref "R52") (pin "1") (pinfunction "1_1") (pintype "passive"))
      (node (ref "R8") (pin "1") (pinfunction "1_1") (pintype "passive"))
      (node (ref "SJ21") (pin "1") (pinfunction "1_1") (pintype "passive"))
    )
    (net (code "20") (name "GPS_HF") (class "Default")
      (node (ref "CON7") (pin "1") (pinfunction "1_1") (pintype "passive"))
      (node (ref "IC11") (pin "11") (pinfunction "11_11") (pintype "input"))
      (node (ref "LFP111") (pin "2") (pinfunction "2_2") (pintype "passive"))
    )
    (net (code "21") (name "GPS_NMEA_RX") (class "Default")
      (node (ref "IC11") (pin "3") (pinfunction "3_3") (pintype "output"))
    )
    (net (code "22") (name "GPS_NMEA_TX") (class "Default")
      (node (ref "IC11") (pin "2") (pinfunction "2_2") (pintype "input"))
      (node (ref "R25") (pin "1") (pinfunction "1_1") (pintype "passive"))
    )
    (net (code "23") (name "GPS_PPS") (class "Default")
      (node (ref "IC11") (pin "4") (pinfunction "4_4") (pintype "output"))
    )
    (net (code "26") (name "Net-(C31-Pad2)") (class "Default")
      (node (ref "C31") (pin "2") (pinfunction "2_2") (pintype "passive"))
      (node (ref "L31") (pin "1") (pinfunction "1_1") (pintype "passive"))
    )
    (net (code "27") (name "Net-(C51-Pad1)") (class "Default")
      (node (ref "C51") (pin "1") (pinfunction "1_1") (pintype "passive"))
      (node (ref "R51") (pin "2") (pinfunction "2_2") (pintype "passive"))
    )
    (net (code "28") (name "Net-(C71-Pad2)") (class "Default")
      (node (ref "C71") (pin "2") (pinfunction "2_2") (pintype "passive"))
      (node (ref "R71") (pin "1") (pinfunction "1_1") (pintype "passive"))
    )
    (net (code "29") (name "Net-(CON2-D+)") (class "Default")
      (node (ref "CON2") (pin "3") (pinfunction "D+_3") (pintype "bidirectional"))
      (node (ref "D4") (pin "C") (pinfunction "C_C") (pintype "passive"))
      (node (ref "R6") (pin "1") (pinfunction "1_1") (pintype "passive"))
      (node (ref "R8") (pin "2") (pinfunction "2_2") (pintype "passive"))
    )
    (net (code "30") (name "Net-(CON2-D-)") (class "Default")
      (node (ref "CON2") (pin "2") (pinfunction "D-_2") (pintype "bidirectional"))
      (node (ref "D3") (pin "C") (pinfunction "C_C") (pintype "passive"))
      (node (ref "R5") (pin "1") (pinfunction "1_1") (pintype "passive"))
      (node (ref "R7") (pin "1") (pinfunction "1_1") (pintype "passive"))
    )
    (net (code "31") (name "Net-(CON2-VBUS)") (class "Default")
      (node (ref "CON2") (pin "1") (pinfunction "VBUS_1") (pintype "bidirectional"))
      (node (ref "RPOLY3") (pin "1") (pinfunction "1_1") (pintype "passive"))
    )
    (net (code "32") (name "Net-(CON4-Pad1)") (class "Default")
      (node (ref "CON4") (pin "1") (pinfunction "1_1") (pintype "passive"))
      (node (ref "R22") (pin "1") (pinfunction "1_1") (pintype "passive"))
    )
    (net (code "33") (name "Net-(CON4-Pad2)") (class "Default")
      (node (ref "CON4") (pin "2") (pinfunction "2_2") (pintype "passive"))
      (node (ref "JP2") (pin "1") (pinfunction "1_1") (pintype "passive"))
    )
    (net (code "34") (name "Net-(CON4-Pad3)") (class "Default")
      (node (ref "CON4") (pin "3") (pinfunction "3_3") (pintype "passive"))
      (node (ref "R23") (pin "2") (pinfunction "2_2") (pintype "passive"))
    )
    (net (code "35") (name "Net-(CON4-Pad5)") (class "Default")
      (node (ref "CON4") (pin "5") (pinfunction "5_5") (pintype "passive"))
      (node (ref "CON5") (pin "6") (pinfunction "6_6") (pintype "passive"))
      (node (ref "JP1") (pin "2") (pinfunction "2_2") (pintype "passive"))
      (node (ref "R21") (pin "2") (pinfunction "2_2") (pintype "passive"))
    )
    (net (code "36") (name "Net-(CON5-Pad4)") (class "Default")
      (node (ref "CON5") (pin "4") (pinfunction "4_4") (pintype "passive"))
      (node (ref "R81") (pin "1") (pinfunction "1_1") (pintype "passive"))
    )
    (net (code "37") (name "Net-(IC4-VC)") (class "Default")
      (node (ref "D202") (pin "A") (pinfunction "A_A") (pintype "passive"))
      (node (ref "IC4") (pin "1") (pinfunction "VC_1") (pintype "input"))
    )
    (net (code "38") (name "Net-(IC4-VCC_3V0)") (class "Default")
      (node (ref "C221") (pin "1") (pinfunction "1_1") (pintype "passive"))
      (node (ref "D221") (pin "C") (pinfunction "C_C") (pintype "passive"))
      (node (ref "IC4") (pin "4") (pinfunction "VCC_3V0_4") (pintype "power_in"))
      (node (ref "R221") (pin "2") (pinfunction "2_2") (pintype "passive"))
    )
    (net (code "39") (name "Net-(IC11-Pad14)") (class "Default")
      (node (ref "IC11") (pin "14") (pinfunction "14_14") (pintype "power_in"))
      (node (ref "LFP111") (pin "1") (pinfunction "1_1") (pintype "passive"))
    )
    (net (code "40") (name "Net-(JP1-Pad1)") (class "Default")
      (node (ref "JP1") (pin "1") (pinfunction "1_1") (pintype "passive"))
      (node (ref "R41") (pin "2") (pinfunction "2_2") (pintype "passive"))
    )
    (net (code "45") (name "PWR_3V3_GPS") (class "Default")
      (node (ref "C111") (pin "1") (pinfunction "1_1") (pintype "passive"))
      (node (ref "IC11") (pin "8") (pinfunction "8_8") (pintype "power_in"))
    )
    (net (code "47") (name "PWR_BACKUP_GPS") (class "Default")
      (node (ref "C81") (pin "+") (pinfunction "+_+") (pintype "passive"))
      (node (ref "D82") (pin "3") (pinfunction "C_3") (pintype "passive"))
      (node (ref "IC11") (pin "6") (pinfunction "6_6") (pintype "power_in"))
    )
    (net (code "48") (name "REFC_10MHZ") (class "Default")
      (node (ref "CON1") (pin "1") (pinfunction "1_1") (pintype "passive"))
    )
    (net (code "50") (name "SIG_CH0_I") (class "Default")
      (node (ref "CON3") (pin "1") (pinfunction "1_1") (pintype "passive"))
    )
    (net (code "51") (name "SIG_CH0_Q") (class "Default")
      (node (ref "CON8") (pin "1") (pinfunction "1_1") (pintype "passive"))
    )
    (net (code "52") (name "SIG_CH1_I") (class "Default")
      (node (ref "CON9") (pin "1") (pinfunction "1_1") (pintype "passive"))
    )
    (net (code "53") (name "SIG_CH1_Q") (class "Default")
      (node (ref "CON10") (pin "1") (pinfunction "1_1") (pintype "passive"))
    )
    (net (code "54") (name "USB_5V") (class "Default")
      (node (ref "C3") (pin "+") (pinfunction "+_+") (pintype "passive"))
      (node (ref "C4") (pin "1") (pinfunction "1_1") (pintype "passive"))
      (node (ref "RPOLY3") (pin "2") (pinfunction "2_2") (pintype "passive"))
    )
    (net (code "55") (name "USB_DISC") (class "Default")
      (node (ref "R7") (pin "2") (pinfunction "2_2") (pintype "passive"))
    )
    (net (code "56") (name "USB_D_MNS") (class "Default")
      (node (ref "R5") (pin "2") (pinfunction "2_2") (pintype "passive"))
    )
    (net (code "57") (name "USB_D_PLS") (class "Default")
      (node (ref "R6") (pin "2") (pinfunction "2_2") (pintype "passive"))
    )
    (net (code "58") (name "VCC") (class "Default")
      (node (ref "C911") (pin "1") (pinfunction "1_1") (pintype "passive"))
      (node (ref "C931") (pin "1") (pinfunction "1_1") (pintype "passive"))
      (node (ref "C951") (pin "1") (pinfunction "1_1") (pintype "passive"))
      (node (ref "CON5") (pin "7") (pinfunction "7_7") (pintype "passive"))
      (node (ref "CON6") (pin "3") (pinfunction "3_3") (pintype "passive"))
      (node (ref "IC3") (pin "16") (pinfunction "VCC_16") (pintype "power_in"))
      (node (ref "JP2") (pin "2") (pinfunction "2_2") (pintype "passive"))
      (node (ref "L31") (pin "2") (pinfunction "2_2") (pintype "passive"))
      (node (ref "R41") (pin "1") (pinfunction "1_1") (pintype "passive"))
      (node (ref "R71") (pin "2") (pinfunction "2_2") (pintype "passive"))
      (node (ref "R81") (pin "2") (pinfunction "2_2") (pintype "passive"))
    )
    (net (code "60") (name "unconnected-(C32-Pad1)") (class "Default")
      (node (ref "C32") (pin "1") (pinfunction "1_1") (pintype "passive"))
    )
    (net (code "61") (name "unconnected-(C71-Pad1)") (class "Default")
      (node (ref "C71") (pin "1") (pinfunction "1_1") (pintype "passive"))
    )
    (net (code "62") (name "unconnected-(C72-Pad1)") (class "Default")
      (node (ref "C72") (pin "1") (pinfunction "1_1") (pintype "passive"))
    )
    (net (code "63") (name "unconnected-(C72-Pad2)") (class "Default")
      (node (ref "C72") (pin "2") (pinfunction "2_2") (pintype "passive"))
    )
    (net (code "64") (name "unconnected-(CON4-Pad4)") (class "Default")
      (node (ref "CON4") (pin "4") (pinfunction "4_4") (pintype "passive"))
    )
    (net (code "65") (name "unconnected-(CON5-Pad1)") (class "Default")
      (node (ref "CON5") (pin "1") (pinfunction "1_1") (pintype "passive"))
    )
    (net (code "66") (name "unconnected-(CON5-Pad3)") (class "Default")
      (node (ref "CON5") (pin "3") (pinfunction "3_3") (pintype "passive"))
    )
    (net (code "67") (name "unconnected-(CON5-Pad5)") (class "Default")
      (node (ref "CON5") (pin "5") (pinfunction "5_5") (pintype "passive"))
    )
    (net (code "68") (name "unconnected-(CON5-Pad8)") (class "Default")
      (node (ref "CON5") (pin "8") (pinfunction "8_8") (pintype "passive"))
    )
    (net (code "69") (name "unconnected-(CON5-Pad9)") (class "Default")
      (node (ref "CON5") (pin "9") (pinfunction "9_9") (pintype "passive"))
    )
    (net (code "70") (name "unconnected-(CON6-Pad2)") (class "Default")
      (node (ref "CON6") (pin "2") (pinfunction "2_2") (pintype "passive"))
    )
    (net (code "71") (name "unconnected-(CON6-Pad4)") (class "Default")
      (node (ref "CON6") (pin "4") (pinfunction "4_4") (pintype "passive"))
    )
    (net (code "72") (name "unconnected-(IC4-OUT-Pad3)") (class "Default")
      (node (ref "IC4") (pin "3") (pinfunction "OUT_3") (pintype "output"))
    )
    (net (code "73") (name "unconnected-(IC11-Pad5)") (class "Default")
      (node (ref "IC11") (pin "5") (pinfunction "5_5") (pintype "no_connect"))
    )
    (net (code "74") (name "unconnected-(IC11-Pad7)") (class "Default")
      (node (ref "IC11") (pin "7") (pinfunction "7_7") (pintype "bidirectional"))
    )
    (net (code "75") (name "unconnected-(IC11-Pad9)") (class "Default")
      (node (ref "IC11") (pin "9") (pinfunction "9_9") (pintype "no_connect"))
    )
    (net (code "76") (name "unconnected-(IC11-Pad13)") (class "Default")
      (node (ref "IC11") (pin "13") (pinfunction "13_13") (pintype "no_connect"))
    )
    (net (code "77") (name "unconnected-(IC11-Pad15)") (class "Default")
      (node (ref "IC11") (pin "15") (pinfunction "15_15") (pintype "no_connect"))
    )
    (net (code "78") (name "unconnected-(IC11-Pad16)") (class "Default")
      (node (ref "IC11") (pin "16") (pinfunction "16_16") (pintype "no_connect"))
    )
    (net (code "79") (name "unconnected-(IC11-Pad17)") (class "Default")
      (node (ref "IC11") (pin "17") (pinfunction "17_17") (pintype "no_connect"))
    )
    (net (code "80") (name "unconnected-(IC11-Pad18)") (class "Default")
      (node (ref "IC11") (pin "18") (pinfunction "18_18") (pintype "no_connect"))
    )
    (net (code "81") (name "unconnected-(JP3-Pad2)") (class "Default")
      (node (ref "JP3") (pin "2") (pinfunction "2_2") (pintype "passive"))
    )
    (net (code "82") (name "unconnected-(R10-Pad1)") (class "Default")
      (node (ref "R10") (pin "1") (pinfunction "1_1") (pintype "passive"))
    )
    (net (code "83") (name "unconnected-(R10-Pad2)") (class "Default")
      (node (ref "R10") (pin "2") (pinfunction "2_2") (pintype "passive"))
    )
    (net (code "84") (name "unconnected-(R21-Pad1)") (class "Default")
      (node (ref "R21") (pin "1") (pinfunction "1_1") (pintype "passive"))
    )
    (net (code "85") (name "unconnected-(R22-Pad2)") (class "Default")
      (node (ref "R22") (pin "2") (pinfunction "2_2") (pintype "passive"))
    )
    (net (code "86") (name "unconnected-(R23-Pad1)") (class "Default")
      (node (ref "R23") (pin "1") (pinfunction "1_1") (pintype "passive"))
    )
    (net (code "87") (name "unconnected-(R25-Pad2)") (class "Default")
      (node (ref "R25") (pin "2") (pinfunction "2_2") (pintype "passive"))
    )
    (net (code "88") (name "unconnected-(R51-Pad1)") (class "Default")
      (node (ref "R51") (pin "1") (pinfunction "1_1") (pintype "passive"))
    )
    (net (code "89") (name "unconnected-(R52-Pad2)") (class "Default")
      (node (ref "R52") (pin "2") (pinfunction "2_2") (pintype "passive"))
    )
    (net (code "90") (name "unconnected-(RPOLY2-Pad1)") (class "Default")
      (node (ref "RPOLY2") (pin "1") (pinfunction "1_1") (pintype "passive"))
    )
    (net (code "91") (name "unconnected-(SJ21-Pad2)") (class "Default")
      (node (ref "SJ21") (pin "2") (pinfunction "2_2") (pintype "passive"))
    )
    (net (code "92") (name "unconnected-(SJ22-Pad1)") (class "Default")
      (node (ref "SJ22") (pin "1") (pinfunction "1_1") (pintype "passive"))
    )
  )
)
